# XTIDA-010086_Control_Card_28379.net
KiCad netlist of a schematic drawn in Altium Designer
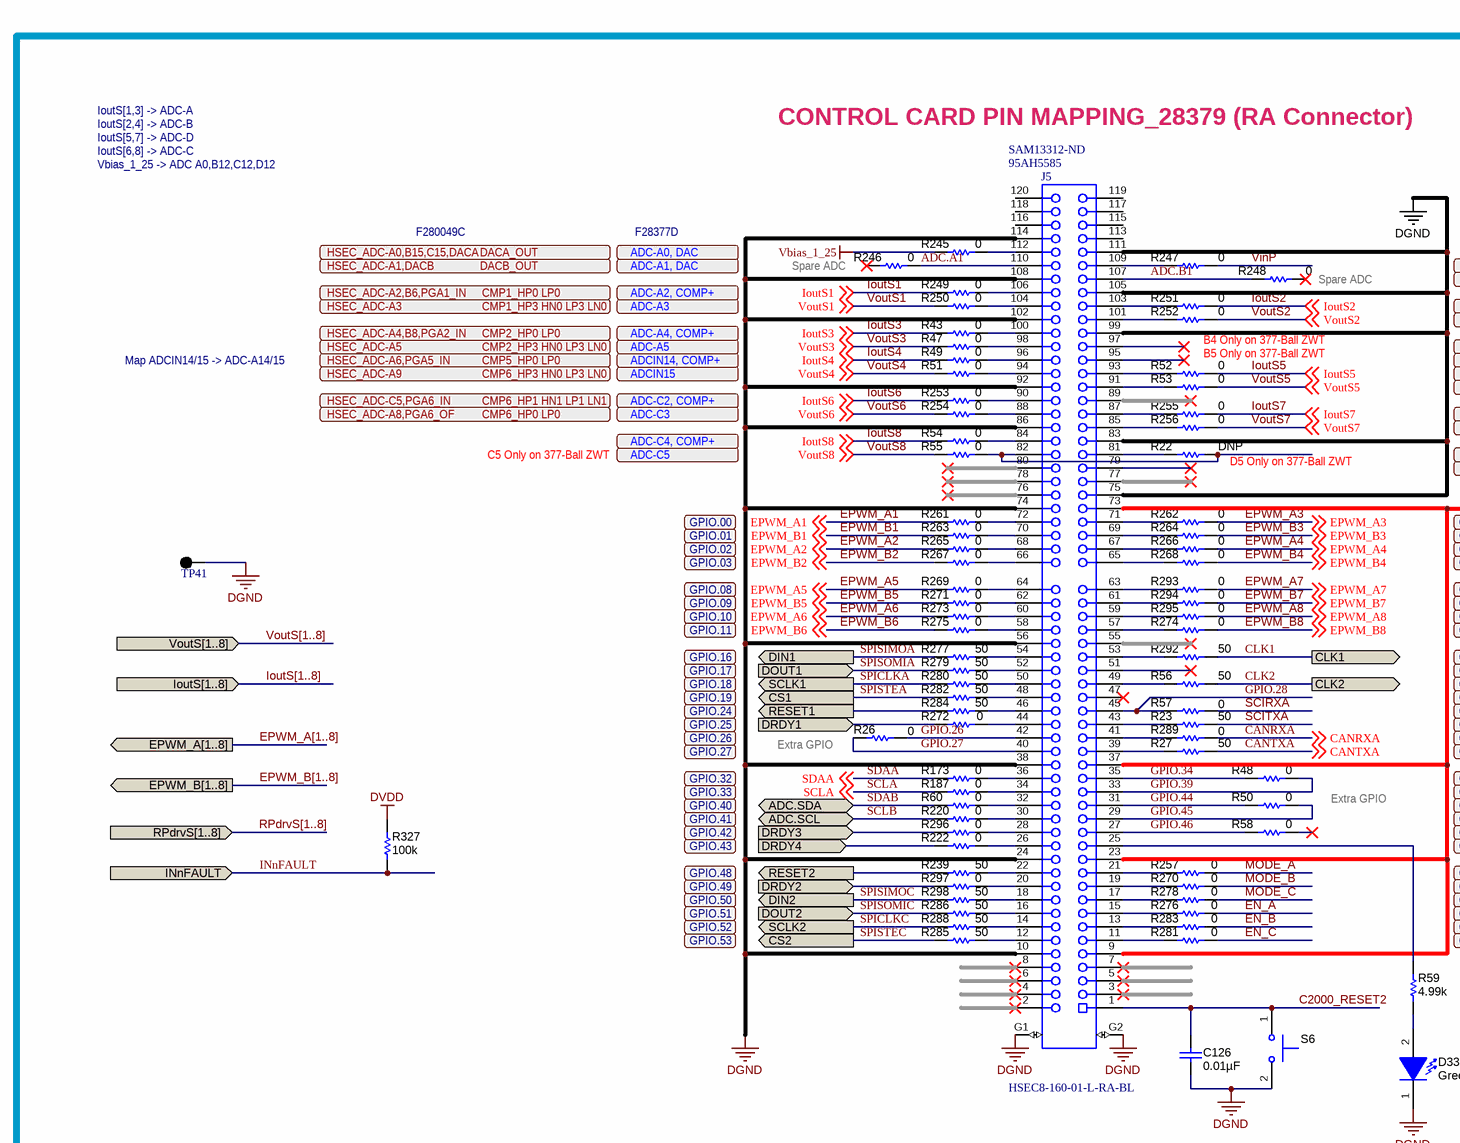
[diagram p0: XTIDA-010086_Control Card_28379.SchDoc, top left]
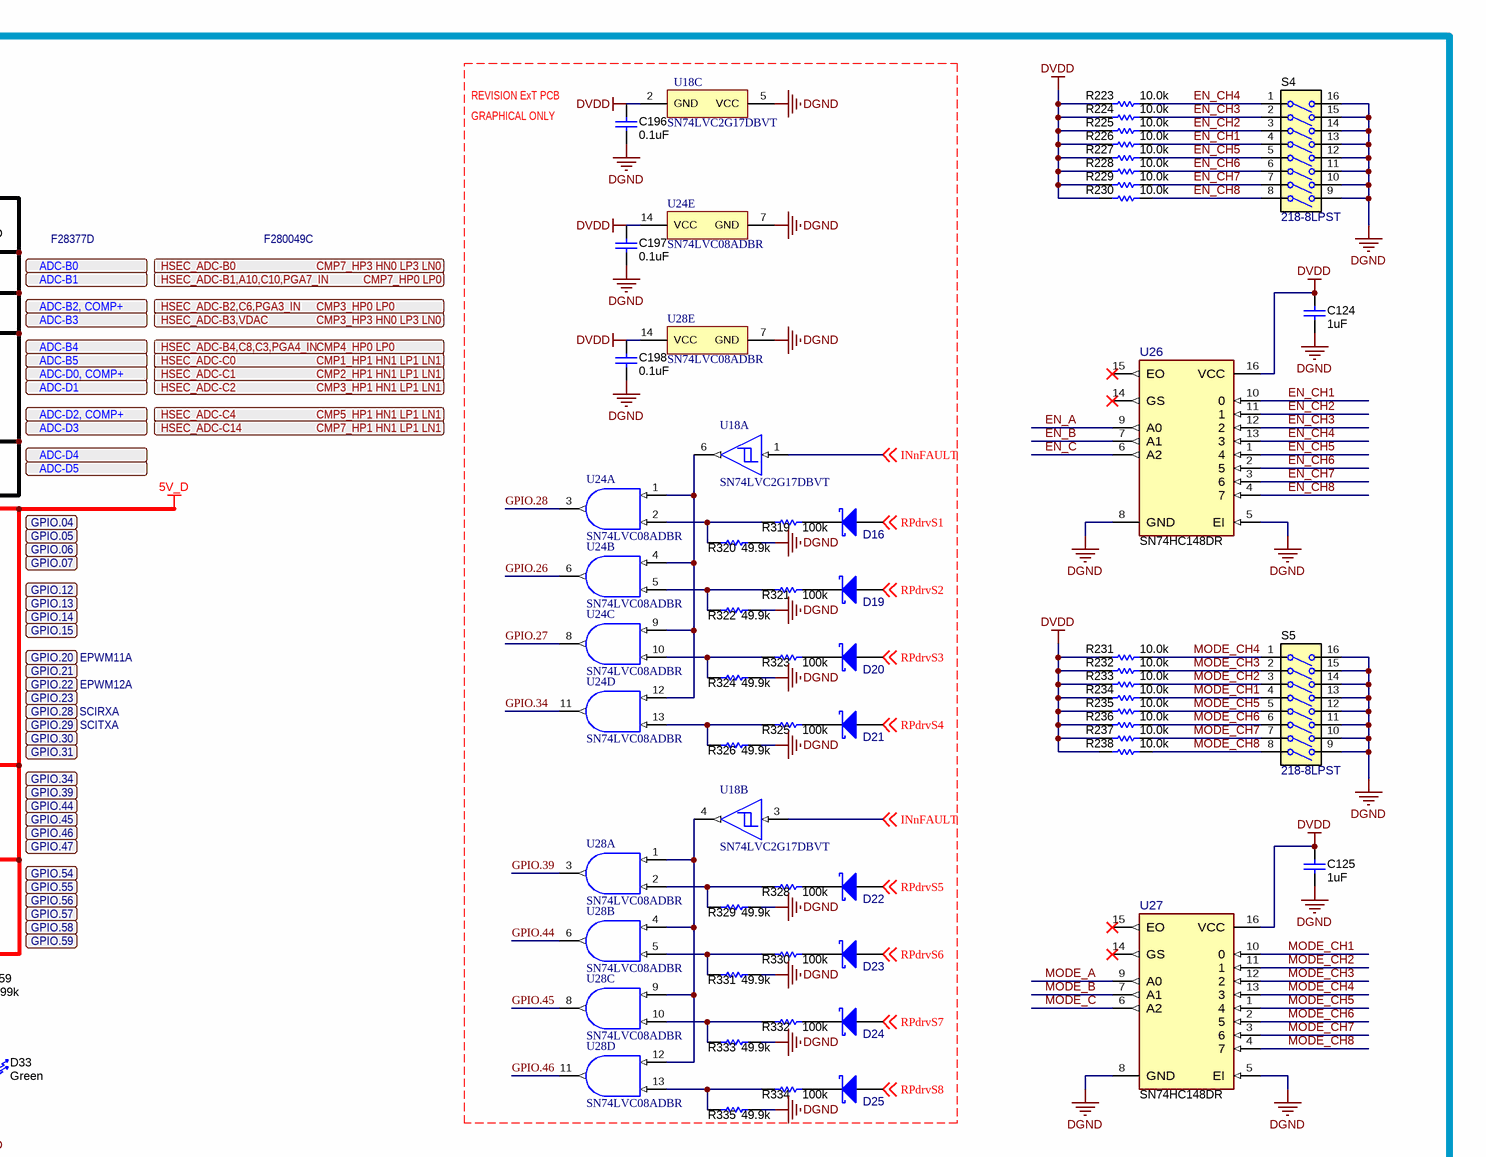
[diagram p1: XTIDA-010086_Control Card_28379.SchDoc, top right]
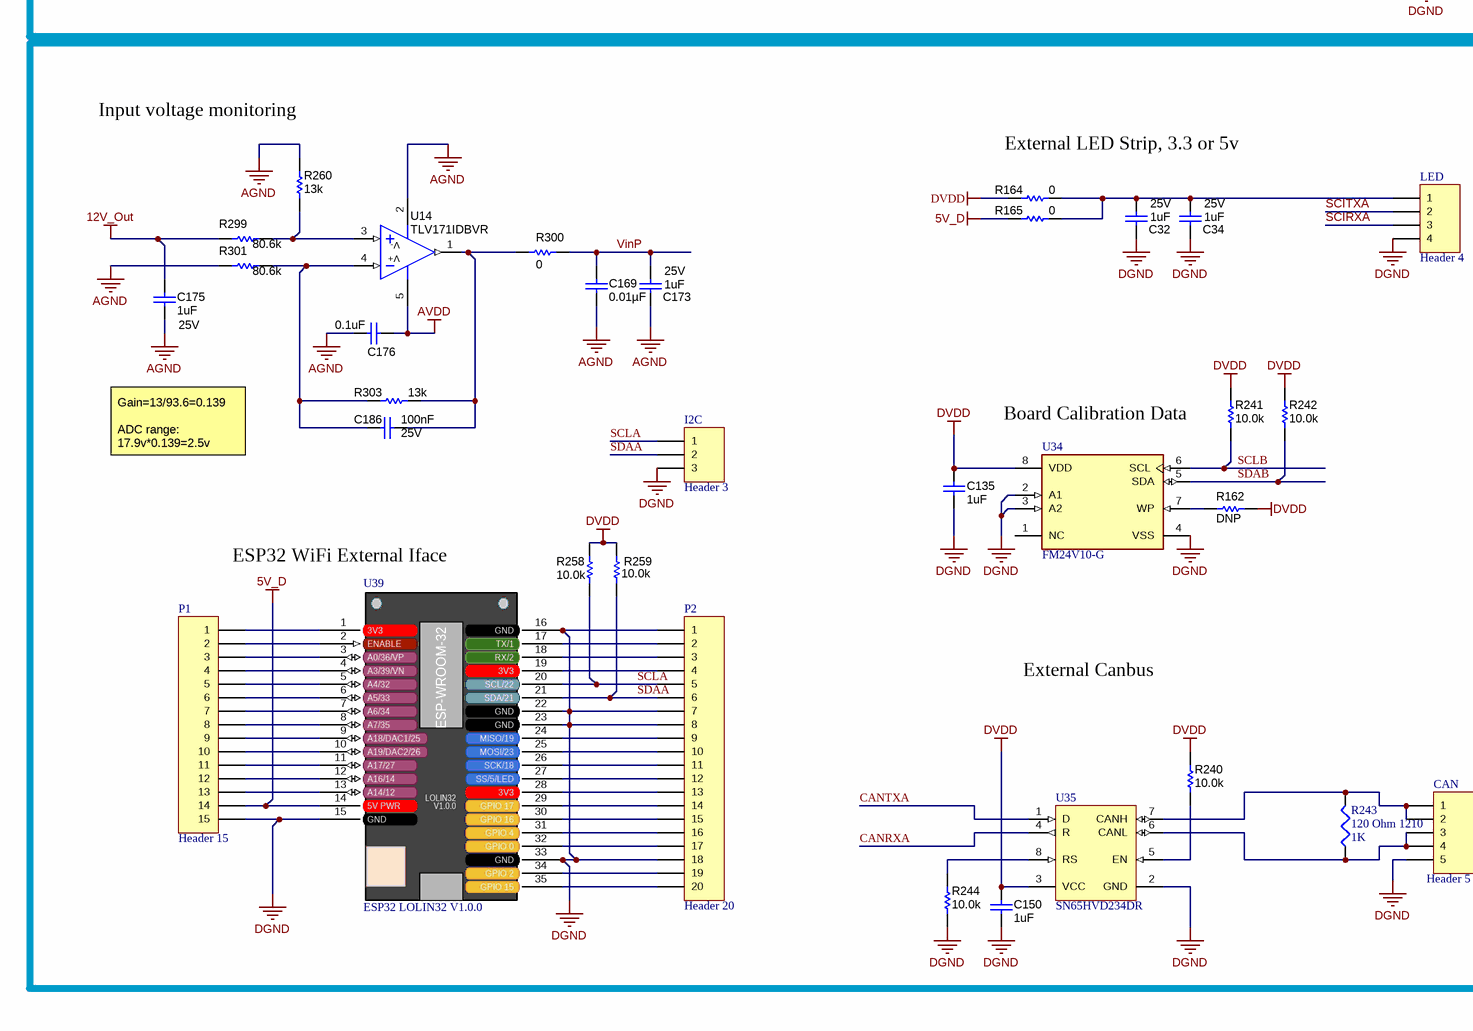
[diagram p2: XTIDA-010086_Control Card_28379.SchDoc, bottom left]
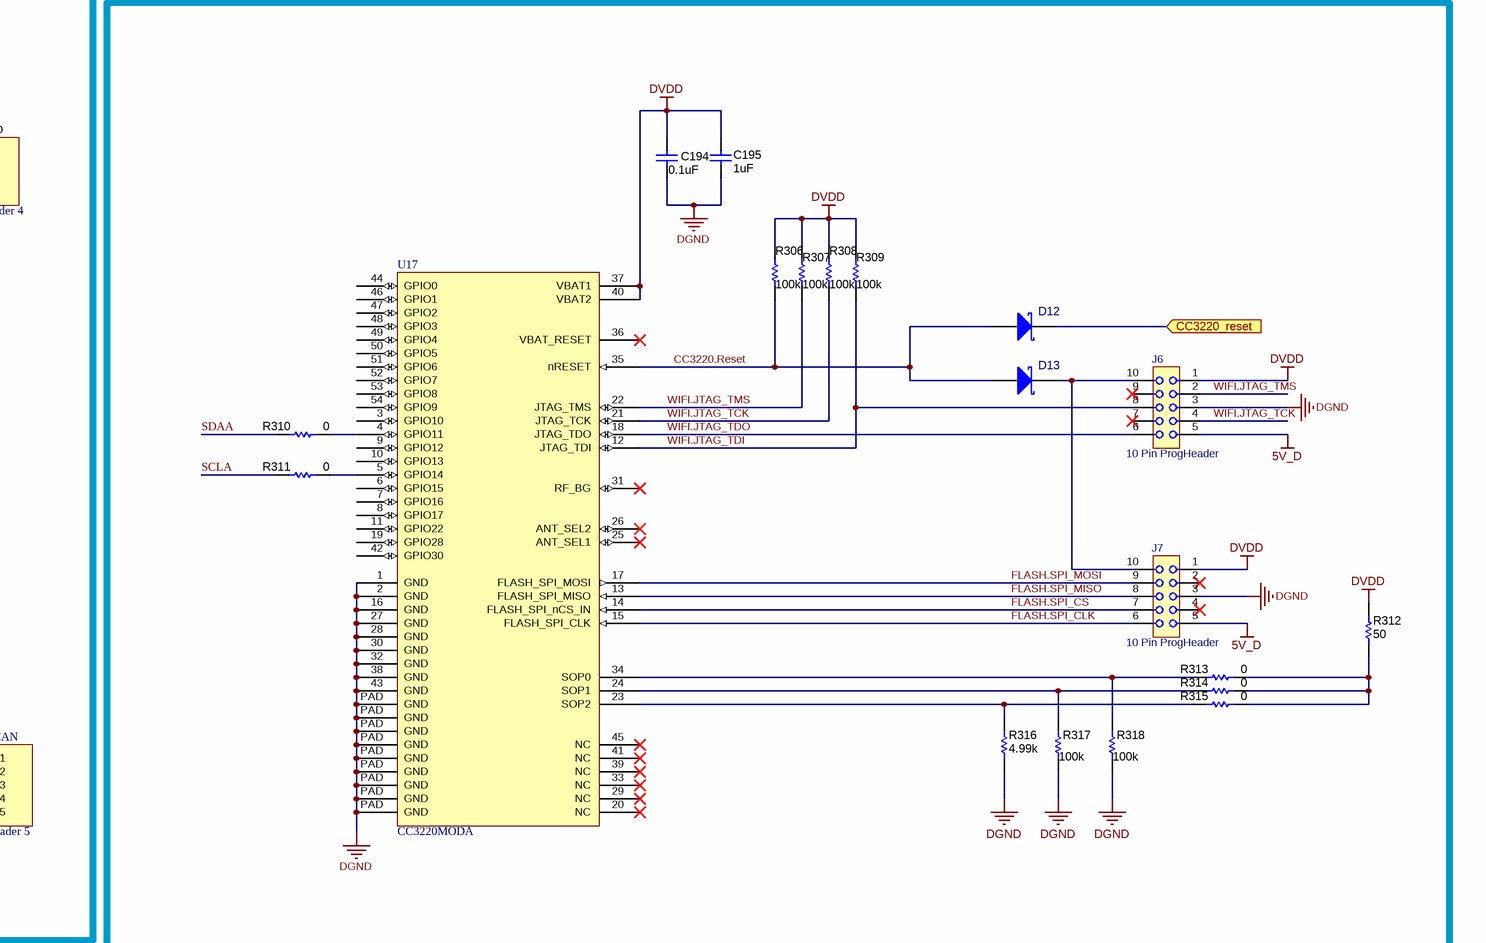
[diagram p3: XTIDA-010086_Control Card_28379.SchDoc, bottom right]

(export (version "E")
  (design (tool "Eeschema 10.0.6"))
  (components
    (comp (ref "C32")
      (value "GRM188R71E105KA12D")
      (footprint "0603")
      (description "CAP, CERM, 1 uF, 25 V, +/- 10%, X7R, 0603")
      (fields
        (field (name "VALUEDISPLAYED") "1uF")
        (field (name "MANUFACTURER") "MuRata")
        (field (name "VDC_V") "25V")
        (field (name "PUBLISHER") "Texas Instruments")
      )
      (libsource (lib "Capacitor_Ceramic") (part "Capacitor"))
    )
    (comp (ref "C34")
      (value "GRM188R71E105KA12D")
      (footprint "0603")
      (description "CAP, CERM, 1 uF, 25 V, +/- 10%, X7R, 0603")
      (fields
        (field (name "VALUEDISPLAYED") "1uF")
        (field (name "MANUFACTURER") "MuRata")
        (field (name "VDC_V") "25V")
        (field (name "PUBLISHER") "Texas Instruments")
      )
      (libsource (lib "Capacitor_Ceramic") (part "Capacitor"))
    )
    (comp (ref "C124")
      (value "GRM188R71E105KA12D")
      (footprint "0603")
      (description "CAP, CERM, 1 uF, 25 V, +/- 10%, X7R, 0603")
      (fields
        (field (name "VALUEDISPLAYED") "1uF")
        (field (name "MANUFACTURER") "MuRata")
        (field (name "PUBLISHER") "Texas Instruments")
      )
      (libsource (lib "Capacitor_Ceramic") (part "Capacitor"))
    )
    (comp (ref "C125")
      (value "GRM188R71E105KA12D")
      (footprint "0603")
      (description "CAP, CERM, 1 uF, 25 V, +/- 10%, X7R, 0603")
      (fields
        (field (name "VALUEDISPLAYED") "1uF")
        (field (name "MANUFACTURER") "MuRata")
        (field (name "PUBLISHER") "Texas Instruments")
      )
      (libsource (lib "Capacitor_Ceramic") (part "Capacitor"))
    )
    (comp (ref "C126")
      (value "C0603C103J3GECAUTO")
      (footprint "0603")
      (description "CAP, CERM, 0.01 µF, 25 V,+/- 5%, C0G/NP0, AEC-Q200 Grade 1, 0603")
      (fields
        (field (name "VALUEDISPLAYED") "0.01µF")
        (field (name "MANUFACTURER") "Kemet")
        (field (name "PUBLISHER") "Texas Instruments")
      )
      (libsource (lib "Capacitor_Ceramic") (part "C0603C103J3GECAUTO"))
    )
    (comp (ref "C135")
      (value "GRM188R71E105KA12D")
      (footprint "0603")
      (description "CAP, CERM, 1 uF, 25 V, +/- 10%, X7R, 0603")
      (fields
        (field (name "VALUEDISPLAYED") "1uF")
        (field (name "MANUFACTURER") "MuRata")
        (field (name "PUBLISHER") "Texas Instruments")
      )
      (libsource (lib "Capacitor_Ceramic") (part "Capacitor"))
    )
    (comp (ref "C150")
      (value "GRM188R71E105KA12D")
      (footprint "0603")
      (description "CAP, CERM, 1 uF, 25 V, +/- 10%, X7R, 0603")
      (fields
        (field (name "VALUEDISPLAYED") "1uF")
        (field (name "MANUFACTURER") "MuRata")
        (field (name "PUBLISHER") "Texas Instruments")
      )
      (libsource (lib "Capacitor_Ceramic") (part "Capacitor"))
    )
    (comp (ref "C169")
      (value "C0603C103J3GECAUTO")
      (footprint "0603")
      (description "CAP, CERM, 0.01 µF, 25 V,+/- 5%, C0G/NP0, AEC-Q200 Grade 1, 0603")
      (fields
        (field (name "VALUEDISPLAYED") "0.01µF")
        (field (name "MANUFACTURER") "Kemet")
        (field (name "PUBLISHER") "Texas Instruments")
      )
      (libsource (lib "Capacitor_Ceramic") (part "C0603C103J3GECAUTO"))
    )
    (comp (ref "C173")
      (value "GRM188R71E105KA12D")
      (footprint "0603")
      (description "CAP, CERM, 1 uF, 25 V, +/- 10%, X7R, 0603")
      (fields
        (field (name "VALUEDISPLAYED") "1uF")
        (field (name "MANUFACTURER") "MuRata")
        (field (name "VDC_V") "25V")
        (field (name "PUBLISHER") "Texas Instruments")
      )
      (libsource (lib "Capacitor_Ceramic") (part "Capacitor"))
    )
    (comp (ref "C175")
      (value "GRM188R71E105KA12D")
      (footprint "0603")
      (description "CAP, CERM, 1 uF, 25 V, +/- 10%, X7R, 0603")
      (fields
        (field (name "VALUEDISPLAYED") "1uF")
        (field (name "MANUFACTURER") "MuRata")
        (field (name "VALUE2") "25V")
        (field (name "PUBLISHER") "Texas Instruments")
      )
      (libsource (lib "Capacitor_Ceramic") (part "Capacitor"))
    )
    (comp (ref "C176")
      (value "06033C104JAT2A")
      (footprint "0603")
      (description "CAP, CERM, 0.1 uF, 25 V, +/- 5%, X7R, 0603")
      (fields
        (field (name "VALUEDISPLAYED") "0.1uF")
        (field (name "MANUFACTURER") "AVX")
        (field (name "PUBLISHER") "Texas Instruments")
      )
      (libsource (lib "TIDA-010086") (part "Capacitor"))
    )
    (comp (ref "C186")
      (value "06033C104JAT2A")
      (footprint "0603")
      (description "CAP, CERM, 0.1 uF, 25 V, +/- 5%, X7R, 0603")
      (fields
        (field (name "MANUFACTURER") "AVX")
        (field (name "CAP_F") "100nF")
        (field (name "VALUE2") "25V")
        (field (name "PUBLISHER") "Texas Instruments")
      )
      (libsource (lib "TIDA-010086") (part "Capacitor"))
    )
    (comp (ref "C194")
      (value "06033C104JAT2A")
      (footprint "0603")
      (description "CAP, CERM, 0.1 uF, 25 V, +/- 5%, X7R, 0603")
      (fields
        (field (name "VALUEDISPLAYED") "0.1uF")
        (field (name "MANUFACTURER") "AVX")
        (field (name "PUBLISHER") "Texas Instruments")
      )
      (libsource (lib "TIDA-010086") (part "Capacitor"))
    )
    (comp (ref "C195")
      (value "GRM188R71E105KA12D")
      (footprint "0603")
      (description "CAP, CERM, 1 uF, 25 V, +/- 10%, X7R, 0603")
      (fields
        (field (name "VALUEDISPLAYED") "1uF")
        (field (name "MANUFACTURER") "MuRata")
        (field (name "PUBLISHER") "Texas Instruments")
      )
      (libsource (lib "Capacitor_Ceramic") (part "Capacitor"))
    )
    (comp (ref "C196")
      (value "06033C104JAT2A")
      (footprint "0603")
      (description "CAP, CERM, 0.1 uF, 25 V, +/- 5%, X7R, 0603")
      (fields
        (field (name "VALUEDISPLAYED") "0.1uF")
        (field (name "MANUFACTURER") "AVX")
        (field (name "PUBLISHER") "Texas Instruments")
      )
      (libsource (lib "TIDA-010086") (part "Capacitor"))
    )
    (comp (ref "C197")
      (value "06033C104JAT2A")
      (footprint "0603")
      (description "CAP, CERM, 0.1 uF, 25 V, +/- 5%, X7R, 0603")
      (fields
        (field (name "VALUEDISPLAYED") "0.1uF")
        (field (name "MANUFACTURER") "AVX")
        (field (name "PUBLISHER") "Texas Instruments")
      )
      (libsource (lib "TIDA-010086") (part "Capacitor"))
    )
    (comp (ref "C198")
      (value "06033C104JAT2A")
      (footprint "0603")
      (description "CAP, CERM, 0.1 uF, 25 V, +/- 5%, X7R, 0603")
      (fields
        (field (name "VALUEDISPLAYED") "0.1uF")
        (field (name "MANUFACTURER") "AVX")
        (field (name "PUBLISHER") "Texas Instruments")
      )
      (libsource (lib "TIDA-010086") (part "Capacitor"))
    )
    (comp (ref "CAN")
      (value "Header 5")
      (footprint "TERM_BLK_ED555-5DS")
      (description "Header, 5-Pin")
      (fields (field (name "PUBLISHER") "Altium Limited"))
      (libsource (lib "Miscellaneous Connectors") (part "Header 5"))
    )
    (comp (ref "D12")
      (value "NSR0240V2T1G")
      (footprint "SOD-523")
      (description "Diode, Schottky, 40V, 0.25A, SOD-523")
      (fields (field (name "MANUFACTURER") "ON Semiconductor") (field (name "PUBLISHER") "Texas Instruments"))
      (libsource (lib "Diode") (part "NSR0240V2T1G"))
    )
    (comp (ref "D13")
      (value "NSR0240V2T1G")
      (footprint "SOD-523")
      (description "Diode, Schottky, 40V, 0.25A, SOD-523")
      (fields (field (name "MANUFACTURER") "ON Semiconductor") (field (name "PUBLISHER") "Texas Instruments"))
      (libsource (lib "Diode") (part "NSR0240V2T1G"))
    )
    (comp (ref "D16")
      (value "NSR0240V2T1G")
      (footprint "SOD-523")
      (description "Diode, Schottky, 40V, 0.25A, SOD-523")
      (fields (field (name "MANUFACTURER") "ON Semiconductor") (field (name "PUBLISHER") "Texas Instruments"))
      (libsource (lib "Diode") (part "NSR0240V2T1G"))
    )
    (comp (ref "D19")
      (value "NSR0240V2T1G")
      (footprint "SOD-523")
      (description "Diode, Schottky, 40V, 0.25A, SOD-523")
      (fields (field (name "MANUFACTURER") "ON Semiconductor") (field (name "PUBLISHER") "Texas Instruments"))
      (libsource (lib "Diode") (part "NSR0240V2T1G"))
    )
    (comp (ref "D20")
      (value "NSR0240V2T1G")
      (footprint "SOD-523")
      (description "Diode, Schottky, 40V, 0.25A, SOD-523")
      (fields (field (name "MANUFACTURER") "ON Semiconductor") (field (name "PUBLISHER") "Texas Instruments"))
      (libsource (lib "Diode") (part "NSR0240V2T1G"))
    )
    (comp (ref "D21")
      (value "NSR0240V2T1G")
      (footprint "SOD-523")
      (description "Diode, Schottky, 40V, 0.25A, SOD-523")
      (fields (field (name "MANUFACTURER") "ON Semiconductor") (field (name "PUBLISHER") "Texas Instruments"))
      (libsource (lib "Diode") (part "NSR0240V2T1G"))
    )
    (comp (ref "D22")
      (value "NSR0240V2T1G")
      (footprint "SOD-523")
      (description "Diode, Schottky, 40V, 0.25A, SOD-523")
      (fields (field (name "MANUFACTURER") "ON Semiconductor") (field (name "PUBLISHER") "Texas Instruments"))
      (libsource (lib "Diode") (part "NSR0240V2T1G"))
    )
    (comp (ref "D23")
      (value "NSR0240V2T1G")
      (footprint "SOD-523")
      (description "Diode, Schottky, 40V, 0.25A, SOD-523")
      (fields (field (name "MANUFACTURER") "ON Semiconductor") (field (name "PUBLISHER") "Texas Instruments"))
      (libsource (lib "Diode") (part "NSR0240V2T1G"))
    )
    (comp (ref "D24")
      (value "NSR0240V2T1G")
      (footprint "SOD-523")
      (description "Diode, Schottky, 40V, 0.25A, SOD-523")
      (fields (field (name "MANUFACTURER") "ON Semiconductor") (field (name "PUBLISHER") "Texas Instruments"))
      (libsource (lib "Diode") (part "NSR0240V2T1G"))
    )
    (comp (ref "D25")
      (value "NSR0240V2T1G")
      (footprint "SOD-523")
      (description "Diode, Schottky, 40V, 0.25A, SOD-523")
      (fields (field (name "MANUFACTURER") "ON Semiconductor") (field (name "PUBLISHER") "Texas Instruments"))
      (libsource (lib "Diode") (part "NSR0240V2T1G"))
    )
    (comp (ref "D33")
      (value "Green")
      (footprint "WL-SMCW_GREEN")
      (description "LED, Green, SMD")
      (fields
        (field (name "MANUFACTURER") "Wurth Elektronik")
        (field (name "PARTNUMBER") "150060VS75000")
        (field (name "PUBLISHER") "Texas Instruments")
      )
      (libsource (lib "LED") (part "150060VS75000"))
    )
    (comp (ref "I2C")
      (value "Header 3")
      (footprint "TERM_BLK_ED555-3DS")
      (description "Header, 3-Pin")
      (fields (field (name "PUBLISHER") "Altium Limited"))
      (libsource (lib "Miscellaneous Connectors") (part "Header 3"))
    )
    (comp (ref "J5")
      (value "HSEC8-160-01-L-RA-BL")
      (footprint "HSEC8-160-01-X-RA-BL")
      (description "0.8MM HIGH SPEED ASSEMBLY.")
      (fields
        (field (name "MP") "HSEC8-160-01-X-RA-BL")
        (field (name "SUPPLIER PART NUMBER 1") "95AH5585")
        (field (name "SUPPLIER PART NUMBER 2") "SAM13312-ND")
      )
      (libsource (lib "TIDA-010086") (part "HSEC8-160-01-X-RA-BL"))
    )
    (comp (ref "J6")
      (value "10 Pin ProgHeader")
      (footprint "TC2050-NL-SMD_W/MOUNT")
      (description "do not populate, RoHS compliant")
      (libsource (lib "Ongyi") (part "10 Pin ProgHeader"))
    )
    (comp (ref "J7")
      (value "10 Pin ProgHeader")
      (footprint "TC2050-NL-SMD_W/mount")
      (description "do not populate, RoHS compliant")
      (libsource (lib "Ongyi") (part "10 Pin ProgHeader"))
    )
    (comp (ref "LED")
      (value "Header 4")
      (footprint "TERM_BLK_ED555-4DS")
      (description "Header, 4-Pin")
      (fields (field (name "PUBLISHER") "Altium Limited"))
      (libsource (lib "Miscellaneous Connectors") (part "Header 4"))
    )
    (comp (ref "P1")
      (value "Header 15")
      (footprint "HDR1X15")
      (description "Header, 15-Pin")
      (fields (field (name "PUBLISHER") "Altium Limited"))
      (libsource (lib "Miscellaneous Connectors") (part "Header 15"))
    )
    (comp (ref "P2")
      (value "Header 20")
      (footprint "HDR1X20")
      (description "Header, 20-Pin")
      (fields (field (name "PUBLISHER") "Altium Limited"))
      (libsource (lib "Miscellaneous Connectors") (part "Header 20"))
    )
    (comp (ref "R22")
      (value "CRCW04020000Z0ED")
      (footprint "0402")
      (description "RES, 0, 5%, 0.063 W, 0402")
      (fields
        (field (name "VALUEDISPLAYED") "DNP")
        (field (name "MANUFACTURER") "Vishay-Dale")
        (field (name "PUBLISHER") "Texas Instruments")
      )
      (libsource (lib "Resistor_0402") (part "CRCW04020000Z0ED"))
    )
    (comp (ref "R23")
      (value "FC0402E50R0BST1")
      (footprint "0402")
      (description "RES, 50, 0.1%, 0.05 W, 0402")
      (fields
        (field (name "VALUEDISPLAYED") "50")
        (field (name "MANUFACTURER") "Vishay-Dale")
        (field (name "PUBLISHER") "Texas Instruments")
      )
      (libsource (lib "Resistor_0402") (part "FC0402E50R0BST1"))
    )
    (comp (ref "R26")
      (value "CRCW04020000Z0ED")
      (footprint "0402")
      (description "RES, 0, 5%, 0.063 W, 0402")
      (fields
        (field (name "VALUEDISPLAYED") "0")
        (field (name "MANUFACTURER") "Vishay-Dale")
        (field (name "PUBLISHER") "Texas Instruments")
      )
      (libsource (lib "Resistor_0402") (part "CRCW04020000Z0ED"))
    )
    (comp (ref "R27")
      (value "FC0402E50R0BST1")
      (footprint "0402")
      (description "RES, 50, 0.1%, 0.05 W, 0402")
      (fields
        (field (name "VALUEDISPLAYED") "50")
        (field (name "MANUFACTURER") "Vishay-Dale")
        (field (name "PUBLISHER") "Texas Instruments")
      )
      (libsource (lib "Resistor_0402") (part "FC0402E50R0BST1"))
    )
    (comp (ref "R43")
      (value "CRCW04020000Z0ED")
      (footprint "0402")
      (description "RES, 0, 5%, 0.063 W, 0402")
      (fields
        (field (name "VALUEDISPLAYED") "0")
        (field (name "MANUFACTURER") "Vishay-Dale")
        (field (name "PUBLISHER") "Texas Instruments")
      )
      (libsource (lib "Resistor_0402") (part "CRCW04020000Z0ED"))
    )
    (comp (ref "R47")
      (value "CRCW04020000Z0ED")
      (footprint "0402")
      (description "RES, 0, 5%, 0.063 W, 0402")
      (fields
        (field (name "VALUEDISPLAYED") "0")
        (field (name "MANUFACTURER") "Vishay-Dale")
        (field (name "PUBLISHER") "Texas Instruments")
      )
      (libsource (lib "Resistor_0402") (part "CRCW04020000Z0ED"))
    )
    (comp (ref "R48")
      (value "CRCW04020000Z0ED")
      (footprint "0402")
      (description "RES, 0, 5%, 0.063 W, 0402")
      (fields
        (field (name "VALUEDISPLAYED") "0")
        (field (name "MANUFACTURER") "Vishay-Dale")
        (field (name "PUBLISHER") "Texas Instruments")
      )
      (libsource (lib "Resistor_0402") (part "CRCW04020000Z0ED"))
    )
    (comp (ref "R49")
      (value "CRCW04020000Z0ED")
      (footprint "0402")
      (description "RES, 0, 5%, 0.063 W, 0402")
      (fields
        (field (name "VALUEDISPLAYED") "0")
        (field (name "MANUFACTURER") "Vishay-Dale")
        (field (name "PUBLISHER") "Texas Instruments")
      )
      (libsource (lib "Resistor_0402") (part "CRCW04020000Z0ED"))
    )
    (comp (ref "R50")
      (value "CRCW04020000Z0ED")
      (footprint "0402")
      (description "RES, 0, 5%, 0.063 W, 0402")
      (fields
        (field (name "VALUEDISPLAYED") "0")
        (field (name "MANUFACTURER") "Vishay-Dale")
        (field (name "PUBLISHER") "Texas Instruments")
      )
      (libsource (lib "Resistor_0402") (part "CRCW04020000Z0ED"))
    )
    (comp (ref "R51")
      (value "CRCW04020000Z0ED")
      (footprint "0402")
      (description "RES, 0, 5%, 0.063 W, 0402")
      (fields
        (field (name "VALUEDISPLAYED") "0")
        (field (name "MANUFACTURER") "Vishay-Dale")
        (field (name "PUBLISHER") "Texas Instruments")
      )
      (libsource (lib "Resistor_0402") (part "CRCW04020000Z0ED"))
    )
    (comp (ref "R52")
      (value "CRCW04020000Z0ED")
      (footprint "0402")
      (description "RES, 0, 5%, 0.063 W, 0402")
      (fields
        (field (name "VALUEDISPLAYED") "0")
        (field (name "MANUFACTURER") "Vishay-Dale")
        (field (name "PUBLISHER") "Texas Instruments")
      )
      (libsource (lib "Resistor_0402") (part "CRCW04020000Z0ED"))
    )
    (comp (ref "R53")
      (value "CRCW04020000Z0ED")
      (footprint "0402")
      (description "RES, 0, 5%, 0.063 W, 0402")
      (fields
        (field (name "VALUEDISPLAYED") "0")
        (field (name "MANUFACTURER") "Vishay-Dale")
        (field (name "PUBLISHER") "Texas Instruments")
      )
      (libsource (lib "Resistor_0402") (part "CRCW04020000Z0ED"))
    )
    (comp (ref "R54")
      (value "CRCW04020000Z0ED")
      (footprint "0402")
      (description "RES, 0, 5%, 0.063 W, 0402")
      (fields
        (field (name "VALUEDISPLAYED") "0")
        (field (name "MANUFACTURER") "Vishay-Dale")
        (field (name "PUBLISHER") "Texas Instruments")
      )
      (libsource (lib "Resistor_0402") (part "CRCW04020000Z0ED"))
    )
    (comp (ref "R55")
      (value "CRCW04020000Z0ED")
      (footprint "0402")
      (description "RES, 0, 5%, 0.063 W, 0402")
      (fields
        (field (name "VALUEDISPLAYED") "0")
        (field (name "MANUFACTURER") "Vishay-Dale")
        (field (name "PUBLISHER") "Texas Instruments")
      )
      (libsource (lib "Resistor_0402") (part "CRCW04020000Z0ED"))
    )
    (comp (ref "R56")
      (value "FC0402E50R0BST1")
      (footprint "0402")
      (description "RES, 50, 0.1%, 0.05 W, 0402")
      (fields
        (field (name "VALUEDISPLAYED") "50")
        (field (name "MANUFACTURER") "Vishay-Dale")
        (field (name "PUBLISHER") "Texas Instruments")
      )
      (libsource (lib "Resistor_0402") (part "FC0402E50R0BST1"))
    )
    (comp (ref "R57")
      (value "CRCW04020000Z0ED")
      (footprint "0402")
      (description "RES, 0, 5%, 0.063 W, 0402")
      (fields
        (field (name "VALUEDISPLAYED") "0")
        (field (name "MANUFACTURER") "Vishay-Dale")
        (field (name "PUBLISHER") "Texas Instruments")
      )
      (libsource (lib "Resistor_0402") (part "CRCW04020000Z0ED"))
    )
    (comp (ref "R58")
      (value "CRCW04020000Z0ED")
      (footprint "0402")
      (description "RES, 0, 5%, 0.063 W, 0402")
      (fields
        (field (name "VALUEDISPLAYED") "0")
        (field (name "MANUFACTURER") "Vishay-Dale")
        (field (name "PUBLISHER") "Texas Instruments")
      )
      (libsource (lib "Resistor_0402") (part "CRCW04020000Z0ED"))
    )
    (comp (ref "R59")
      (value "CRCW06034K99FKEA")
      (footprint "0603L")
      (description "RES, 4.99 k, 1%, 0.1 W, 0603")
      (fields
        (field (name "VALUEDISPLAYED") "4.99k")
        (field (name "MANUFACTURER") "Vishay-Dale")
        (field (name "PUBLISHER") "Texas Instruments")
      )
      (libsource (lib "Resistor_0603") (part "CRCW06034K99FKEA"))
    )
    (comp (ref "R60")
      (value "CRCW04020000Z0ED")
      (footprint "0402")
      (description "RES, 0, 5%, 0.063 W, 0402")
      (fields
        (field (name "VALUEDISPLAYED") "0")
        (field (name "MANUFACTURER") "Vishay-Dale")
        (field (name "PUBLISHER") "Texas Instruments")
      )
      (libsource (lib "Resistor_0402") (part "CRCW04020000Z0ED"))
    )
    (comp (ref "R162")
      (value "CRCW04020000Z0ED")
      (footprint "0402")
      (description "RES, 0, 5%, 0.063 W, 0402")
      (fields
        (field (name "VALUEDISPLAYED") "DNP")
        (field (name "MANUFACTURER") "Vishay-Dale")
        (field (name "PUBLISHER") "Texas Instruments")
      )
      (libsource (lib "Resistor_0402") (part "CRCW04020000Z0ED"))
    )
    (comp (ref "R164")
      (value "CRCW04020000Z0ED")
      (footprint "0402")
      (description "RES, 0, 5%, 0.063 W, 0402")
      (fields
        (field (name "VALUEDISPLAYED") "0")
        (field (name "MANUFACTURER") "Vishay-Dale")
        (field (name "PUBLISHER") "Texas Instruments")
      )
      (libsource (lib "Resistor_0402") (part "CRCW04020000Z0ED"))
    )
    (comp (ref "R165")
      (value "CRCW04020000Z0ED")
      (footprint "0402")
      (description "RES, 0, 5%, 0.063 W, 0402")
      (fields
        (field (name "VALUEDISPLAYED") "0")
        (field (name "MANUFACTURER") "Vishay-Dale")
        (field (name "PUBLISHER") "Texas Instruments")
      )
      (libsource (lib "Resistor_0402") (part "CRCW04020000Z0ED"))
    )
    (comp (ref "R173")
      (value "CRCW04020000Z0ED")
      (footprint "0402")
      (description "RES, 0, 5%, 0.063 W, 0402")
      (fields
        (field (name "VALUEDISPLAYED") "0")
        (field (name "MANUFACTURER") "Vishay-Dale")
        (field (name "PUBLISHER") "Texas Instruments")
      )
      (libsource (lib "Resistor_0402") (part "CRCW04020000Z0ED"))
    )
    (comp (ref "R187")
      (value "CRCW04020000Z0ED")
      (footprint "0402")
      (description "RES, 0, 5%, 0.063 W, 0402")
      (fields
        (field (name "VALUEDISPLAYED") "0")
        (field (name "MANUFACTURER") "Vishay-Dale")
        (field (name "PUBLISHER") "Texas Instruments")
      )
      (libsource (lib "Resistor_0402") (part "CRCW04020000Z0ED"))
    )
    (comp (ref "R220")
      (value "CRCW04020000Z0ED")
      (footprint "0402")
      (description "RES, 0, 5%, 0.063 W, 0402")
      (fields
        (field (name "VALUEDISPLAYED") "0")
        (field (name "MANUFACTURER") "Vishay-Dale")
        (field (name "PUBLISHER") "Texas Instruments")
      )
      (libsource (lib "Resistor_0402") (part "CRCW04020000Z0ED"))
    )
    (comp (ref "R222")
      (value "CRCW04020000Z0ED")
      (footprint "0402")
      (description "RES, 0, 5%, 0.063 W, 0402")
      (fields
        (field (name "VALUEDISPLAYED") "0")
        (field (name "MANUFACTURER") "Vishay-Dale")
        (field (name "PUBLISHER") "Texas Instruments")
      )
      (libsource (lib "Resistor_0402") (part "CRCW04020000Z0ED"))
    )
    (comp (ref "R223")
      (value "CRCW040210K0FKED")
      (footprint "0402")
      (description "RES, 10.0 k, 1%, 0.063 W, 0402")
      (fields
        (field (name "VALUEDISPLAYED") "10.0k")
        (field (name "MANUFACTURER") "Vishay-Dale")
        (field (name "PUBLISHER") "Texas Instruments")
      )
      (libsource (lib "Resistor_0402") (part "CRCW040210K0FKED"))
    )
    (comp (ref "R224")
      (value "CRCW040210K0FKED")
      (footprint "0402")
      (description "RES, 10.0 k, 1%, 0.063 W, 0402")
      (fields
        (field (name "VALUEDISPLAYED") "10.0k")
        (field (name "MANUFACTURER") "Vishay-Dale")
        (field (name "PUBLISHER") "Texas Instruments")
      )
      (libsource (lib "Resistor_0402") (part "CRCW040210K0FKED"))
    )
    (comp (ref "R225")
      (value "CRCW040210K0FKED")
      (footprint "0402")
      (description "RES, 10.0 k, 1%, 0.063 W, 0402")
      (fields
        (field (name "VALUEDISPLAYED") "10.0k")
        (field (name "MANUFACTURER") "Vishay-Dale")
        (field (name "PUBLISHER") "Texas Instruments")
      )
      (libsource (lib "Resistor_0402") (part "CRCW040210K0FKED"))
    )
    (comp (ref "R226")
      (value "CRCW040210K0FKED")
      (footprint "0402")
      (description "RES, 10.0 k, 1%, 0.063 W, 0402")
      (fields
        (field (name "VALUEDISPLAYED") "10.0k")
        (field (name "MANUFACTURER") "Vishay-Dale")
        (field (name "PUBLISHER") "Texas Instruments")
      )
      (libsource (lib "Resistor_0402") (part "CRCW040210K0FKED"))
    )
    (comp (ref "R227")
      (value "CRCW040210K0FKED")
      (footprint "0402")
      (description "RES, 10.0 k, 1%, 0.063 W, 0402")
      (fields
        (field (name "VALUEDISPLAYED") "10.0k")
        (field (name "MANUFACTURER") "Vishay-Dale")
        (field (name "PUBLISHER") "Texas Instruments")
      )
      (libsource (lib "Resistor_0402") (part "CRCW040210K0FKED"))
    )
    (comp (ref "R228")
      (value "CRCW040210K0FKED")
      (footprint "0402")
      (description "RES, 10.0 k, 1%, 0.063 W, 0402")
      (fields
        (field (name "VALUEDISPLAYED") "10.0k")
        (field (name "MANUFACTURER") "Vishay-Dale")
        (field (name "PUBLISHER") "Texas Instruments")
      )
      (libsource (lib "Resistor_0402") (part "CRCW040210K0FKED"))
    )
    (comp (ref "R229")
      (value "CRCW040210K0FKED")
      (footprint "0402")
      (description "RES, 10.0 k, 1%, 0.063 W, 0402")
      (fields
        (field (name "VALUEDISPLAYED") "10.0k")
        (field (name "MANUFACTURER") "Vishay-Dale")
        (field (name "PUBLISHER") "Texas Instruments")
      )
      (libsource (lib "Resistor_0402") (part "CRCW040210K0FKED"))
    )
    (comp (ref "R230")
      (value "CRCW040210K0FKED")
      (footprint "0402")
      (description "RES, 10.0 k, 1%, 0.063 W, 0402")
      (fields
        (field (name "VALUEDISPLAYED") "10.0k")
        (field (name "MANUFACTURER") "Vishay-Dale")
        (field (name "PUBLISHER") "Texas Instruments")
      )
      (libsource (lib "Resistor_0402") (part "CRCW040210K0FKED"))
    )
    (comp (ref "R231")
      (value "CRCW040210K0FKED")
      (footprint "0402")
      (description "RES, 10.0 k, 1%, 0.063 W, 0402")
      (fields
        (field (name "VALUEDISPLAYED") "10.0k")
        (field (name "MANUFACTURER") "Vishay-Dale")
        (field (name "PUBLISHER") "Texas Instruments")
      )
      (libsource (lib "Resistor_0402") (part "CRCW040210K0FKED"))
    )
    (comp (ref "R232")
      (value "CRCW040210K0FKED")
      (footprint "0402")
      (description "RES, 10.0 k, 1%, 0.063 W, 0402")
      (fields
        (field (name "VALUEDISPLAYED") "10.0k")
        (field (name "MANUFACTURER") "Vishay-Dale")
        (field (name "PUBLISHER") "Texas Instruments")
      )
      (libsource (lib "Resistor_0402") (part "CRCW040210K0FKED"))
    )
    (comp (ref "R233")
      (value "CRCW040210K0FKED")
      (footprint "0402")
      (description "RES, 10.0 k, 1%, 0.063 W, 0402")
      (fields
        (field (name "VALUEDISPLAYED") "10.0k")
        (field (name "MANUFACTURER") "Vishay-Dale")
        (field (name "PUBLISHER") "Texas Instruments")
      )
      (libsource (lib "Resistor_0402") (part "CRCW040210K0FKED"))
    )
    (comp (ref "R234")
      (value "CRCW040210K0FKED")
      (footprint "0402")
      (description "RES, 10.0 k, 1%, 0.063 W, 0402")
      (fields
        (field (name "VALUEDISPLAYED") "10.0k")
        (field (name "MANUFACTURER") "Vishay-Dale")
        (field (name "PUBLISHER") "Texas Instruments")
      )
      (libsource (lib "Resistor_0402") (part "CRCW040210K0FKED"))
    )
    (comp (ref "R235")
      (value "CRCW040210K0FKED")
      (footprint "0402")
      (description "RES, 10.0 k, 1%, 0.063 W, 0402")
      (fields
        (field (name "VALUEDISPLAYED") "10.0k")
        (field (name "MANUFACTURER") "Vishay-Dale")
        (field (name "PUBLISHER") "Texas Instruments")
      )
      (libsource (lib "Resistor_0402") (part "CRCW040210K0FKED"))
    )
    (comp (ref "R236")
      (value "CRCW040210K0FKED")
      (footprint "0402")
      (description "RES, 10.0 k, 1%, 0.063 W, 0402")
      (fields
        (field (name "VALUEDISPLAYED") "10.0k")
        (field (name "MANUFACTURER") "Vishay-Dale")
        (field (name "PUBLISHER") "Texas Instruments")
      )
      (libsource (lib "Resistor_0402") (part "CRCW040210K0FKED"))
    )
    (comp (ref "R237")
      (value "CRCW040210K0FKED")
      (footprint "0402")
      (description "RES, 10.0 k, 1%, 0.063 W, 0402")
      (fields
        (field (name "VALUEDISPLAYED") "10.0k")
        (field (name "MANUFACTURER") "Vishay-Dale")
        (field (name "PUBLISHER") "Texas Instruments")
      )
      (libsource (lib "Resistor_0402") (part "CRCW040210K0FKED"))
    )
    (comp (ref "R238")
      (value "CRCW040210K0FKED")
      (footprint "0402")
      (description "RES, 10.0 k, 1%, 0.063 W, 0402")
      (fields
        (field (name "VALUEDISPLAYED") "10.0k")
        (field (name "MANUFACTURER") "Vishay-Dale")
        (field (name "PUBLISHER") "Texas Instruments")
      )
      (libsource (lib "Resistor_0402") (part "CRCW040210K0FKED"))
    )
    (comp (ref "R239")
      (value "FC0402E50R0BST1")
      (footprint "0402")
      (description "RES, 50, 0.1%, 0.05 W, 0402")
      (fields
        (field (name "VALUEDISPLAYED") "50")
        (field (name "MANUFACTURER") "Vishay-Dale")
        (field (name "PUBLISHER") "Texas Instruments")
      )
      (libsource (lib "Resistor_0402") (part "FC0402E50R0BST1"))
    )
    (comp (ref "R240")
      (value "CRCW040210K0FKED")
      (footprint "0402")
      (description "RES, 10.0 k, 1%, 0.063 W, 0402")
      (fields
        (field (name "VALUEDISPLAYED") "10.0k")
        (field (name "MANUFACTURER") "Vishay-Dale")
        (field (name "PUBLISHER") "Texas Instruments")
      )
      (libsource (lib "Resistor_0402") (part "CRCW040210K0FKED"))
    )
    (comp (ref "R241")
      (value "CRCW040210K0FKED")
      (footprint "0402")
      (description "RES, 10.0 k, 1%, 0.063 W, 0402")
      (fields
        (field (name "VALUEDISPLAYED") "10.0k")
        (field (name "MANUFACTURER") "Vishay-Dale")
        (field (name "PUBLISHER") "Texas Instruments")
      )
      (libsource (lib "Resistor_0402") (part "CRCW040210K0FKED"))
    )
    (comp (ref "R242")
      (value "CRCW040210K0FKED")
      (footprint "0402")
      (description "RES, 10.0 k, 1%, 0.063 W, 0402")
      (fields
        (field (name "VALUEDISPLAYED") "10.0k")
        (field (name "MANUFACTURER") "Vishay-Dale")
        (field (name "PUBLISHER") "Texas Instruments")
      )
      (libsource (lib "Resistor_0402") (part "CRCW040210K0FKED"))
    )
    (comp (ref "R243")
      (value "120 Ohm 1210")
      (footprint "14-1210")
      (fields (field (name "ALTIUM_VALUE") "1K") (field (name "PUBLISHER") "Altium Limited"))
      (libsource (lib "Miscellaneous Devices") (part "Res3"))
    )
    (comp (ref "R244")
      (value "CRCW040210K0FKED")
      (footprint "0402")
      (description "RES, 10.0 k, 1%, 0.063 W, 0402")
      (fields
        (field (name "VALUEDISPLAYED") "10.0k")
        (field (name "MANUFACTURER") "Vishay-Dale")
        (field (name "PUBLISHER") "Texas Instruments")
      )
      (libsource (lib "Resistor_0402") (part "CRCW040210K0FKED"))
    )
    (comp (ref "R245")
      (value "CRCW04020000Z0ED")
      (footprint "0402")
      (description "RES, 0, 5%, 0.063 W, 0402")
      (fields
        (field (name "VALUEDISPLAYED") "0")
        (field (name "MANUFACTURER") "Vishay-Dale")
        (field (name "PUBLISHER") "Texas Instruments")
      )
      (libsource (lib "Resistor_0402") (part "CRCW04020000Z0ED"))
    )
    (comp (ref "R246")
      (value "CRCW04020000Z0ED")
      (footprint "0402")
      (description "RES, 0, 5%, 0.063 W, 0402")
      (fields
        (field (name "VALUEDISPLAYED") "0")
        (field (name "MANUFACTURER") "Vishay-Dale")
        (field (name "PUBLISHER") "Texas Instruments")
      )
      (libsource (lib "Resistor_0402") (part "CRCW04020000Z0ED"))
    )
    (comp (ref "R247")
      (value "CRCW04020000Z0ED")
      (footprint "0402")
      (description "RES, 0, 5%, 0.063 W, 0402")
      (fields
        (field (name "VALUEDISPLAYED") "0")
        (field (name "MANUFACTURER") "Vishay-Dale")
        (field (name "PUBLISHER") "Texas Instruments")
      )
      (libsource (lib "Resistor_0402") (part "CRCW04020000Z0ED"))
    )
    (comp (ref "R248")
      (value "CRCW04020000Z0ED")
      (footprint "0402")
      (description "RES, 0, 5%, 0.063 W, 0402")
      (fields
        (field (name "VALUEDISPLAYED") "0")
        (field (name "MANUFACTURER") "Vishay-Dale")
        (field (name "PUBLISHER") "Texas Instruments")
      )
      (libsource (lib "Resistor_0402") (part "CRCW04020000Z0ED"))
    )
    (comp (ref "R249")
      (value "CRCW04020000Z0ED")
      (footprint "0402")
      (description "RES, 0, 5%, 0.063 W, 0402")
      (fields
        (field (name "VALUEDISPLAYED") "0")
        (field (name "MANUFACTURER") "Vishay-Dale")
        (field (name "PUBLISHER") "Texas Instruments")
      )
      (libsource (lib "Resistor_0402") (part "CRCW04020000Z0ED"))
    )
    (comp (ref "R250")
      (value "CRCW04020000Z0ED")
      (footprint "0402")
      (description "RES, 0, 5%, 0.063 W, 0402")
      (fields
        (field (name "VALUEDISPLAYED") "0")
        (field (name "MANUFACTURER") "Vishay-Dale")
        (field (name "PUBLISHER") "Texas Instruments")
      )
      (libsource (lib "Resistor_0402") (part "CRCW04020000Z0ED"))
    )
    (comp (ref "R251")
      (value "CRCW04020000Z0ED")
      (footprint "0402")
      (description "RES, 0, 5%, 0.063 W, 0402")
      (fields
        (field (name "VALUEDISPLAYED") "0")
        (field (name "MANUFACTURER") "Vishay-Dale")
        (field (name "PUBLISHER") "Texas Instruments")
      )
      (libsource (lib "Resistor_0402") (part "CRCW04020000Z0ED"))
    )
    (comp (ref "R252")
      (value "CRCW04020000Z0ED")
      (footprint "0402")
      (description "RES, 0, 5%, 0.063 W, 0402")
      (fields
        (field (name "VALUEDISPLAYED") "0")
        (field (name "MANUFACTURER") "Vishay-Dale")
        (field (name "PUBLISHER") "Texas Instruments")
      )
      (libsource (lib "Resistor_0402") (part "CRCW04020000Z0ED"))
    )
    (comp (ref "R253")
      (value "CRCW04020000Z0ED")
      (footprint "0402")
      (description "RES, 0, 5%, 0.063 W, 0402")
      (fields
        (field (name "VALUEDISPLAYED") "0")
        (field (name "MANUFACTURER") "Vishay-Dale")
        (field (name "PUBLISHER") "Texas Instruments")
      )
      (libsource (lib "Resistor_0402") (part "CRCW04020000Z0ED"))
    )
    (comp (ref "R254")
      (value "CRCW04020000Z0ED")
      (footprint "0402")
      (description "RES, 0, 5%, 0.063 W, 0402")
      (fields
        (field (name "VALUEDISPLAYED") "0")
        (field (name "MANUFACTURER") "Vishay-Dale")
        (field (name "PUBLISHER") "Texas Instruments")
      )
      (libsource (lib "Resistor_0402") (part "CRCW04020000Z0ED"))
    )
    (comp (ref "R255")
      (value "CRCW04020000Z0ED")
      (footprint "0402")
      (description "RES, 0, 5%, 0.063 W, 0402")
      (fields
        (field (name "VALUEDISPLAYED") "0")
        (field (name "MANUFACTURER") "Vishay-Dale")
        (field (name "PUBLISHER") "Texas Instruments")
      )
      (libsource (lib "Resistor_0402") (part "CRCW04020000Z0ED"))
    )
    (comp (ref "R256")
      (value "CRCW04020000Z0ED")
      (footprint "0402")
      (description "RES, 0, 5%, 0.063 W, 0402")
      (fields
        (field (name "VALUEDISPLAYED") "0")
        (field (name "MANUFACTURER") "Vishay-Dale")
        (field (name "PUBLISHER") "Texas Instruments")
      )
      (libsource (lib "Resistor_0402") (part "CRCW04020000Z0ED"))
    )
    (comp (ref "R257")
      (value "CRCW04020000Z0ED")
      (footprint "0402")
      (description "RES, 0, 5%, 0.063 W, 0402")
      (fields
        (field (name "VALUEDISPLAYED") "0")
        (field (name "MANUFACTURER") "Vishay-Dale")
        (field (name "PUBLISHER") "Texas Instruments")
      )
      (libsource (lib "Resistor_0402") (part "CRCW04020000Z0ED"))
    )
    (comp (ref "R258")
      (value "CRCW040210K0FKED")
      (footprint "0402")
      (description "RES, 10.0 k, 1%, 0.063 W, 0402")
      (fields
        (field (name "VALUEDISPLAYED") "10.0k")
        (field (name "MANUFACTURER") "Vishay-Dale")
        (field (name "PUBLISHER") "Texas Instruments")
      )
      (libsource (lib "Resistor_0402") (part "CRCW040210K0FKED"))
    )
    (comp (ref "R259")
      (value "CRCW040210K0FKED")
      (footprint "0402")
      (description "RES, 10.0 k, 1%, 0.063 W, 0402")
      (fields
        (field (name "VALUEDISPLAYED") "10.0k")
        (field (name "MANUFACTURER") "Vishay-Dale")
        (field (name "PUBLISHER") "Texas Instruments")
      )
      (libsource (lib "Resistor_0402") (part "CRCW040210K0FKED"))
    )
    (comp (ref "R260")
      (value "ERJ-3EKF1302V")
      (footprint "0603")
      (description "RES, 13 k, 0.1%, 0.1 W, 0603")
      (fields
        (field (name "MANUFACTURER") "Yageo America")
        (field (name "VALUEDISPLAYED") "13k")
        (field (name "PUBLISHER") "Texas Instruments")
      )
      (libsource (lib "TIDA-010086") (part "Resistor"))
    )
    (comp (ref "R261")
      (value "CRCW04020000Z0ED")
      (footprint "0402")
      (description "RES, 0, 5%, 0.063 W, 0402")
      (fields
        (field (name "VALUEDISPLAYED") "0")
        (field (name "MANUFACTURER") "Vishay-Dale")
        (field (name "PUBLISHER") "Texas Instruments")
      )
      (libsource (lib "Resistor_0402") (part "CRCW04020000Z0ED"))
    )
    (comp (ref "R262")
      (value "CRCW04020000Z0ED")
      (footprint "0402")
      (description "RES, 0, 5%, 0.063 W, 0402")
      (fields
        (field (name "VALUEDISPLAYED") "0")
        (field (name "MANUFACTURER") "Vishay-Dale")
        (field (name "PUBLISHER") "Texas Instruments")
      )
      (libsource (lib "Resistor_0402") (part "CRCW04020000Z0ED"))
    )
    (comp (ref "R263")
      (value "CRCW04020000Z0ED")
      (footprint "0402")
      (description "RES, 0, 5%, 0.063 W, 0402")
      (fields
        (field (name "VALUEDISPLAYED") "0")
        (field (name "MANUFACTURER") "Vishay-Dale")
        (field (name "PUBLISHER") "Texas Instruments")
      )
      (libsource (lib "Resistor_0402") (part "CRCW04020000Z0ED"))
    )
    (comp (ref "R264")
      (value "CRCW04020000Z0ED")
      (footprint "0402")
      (description "RES, 0, 5%, 0.063 W, 0402")
      (fields
        (field (name "VALUEDISPLAYED") "0")
        (field (name "MANUFACTURER") "Vishay-Dale")
        (field (name "PUBLISHER") "Texas Instruments")
      )
      (libsource (lib "Resistor_0402") (part "CRCW04020000Z0ED"))
    )
    (comp (ref "R265")
      (value "CRCW04020000Z0ED")
      (footprint "0402")
      (description "RES, 0, 5%, 0.063 W, 0402")
      (fields
        (field (name "VALUEDISPLAYED") "0")
        (field (name "MANUFACTURER") "Vishay-Dale")
        (field (name "PUBLISHER") "Texas Instruments")
      )
      (libsource (lib "Resistor_0402") (part "CRCW04020000Z0ED"))
    )
    (comp (ref "R266")
      (value "CRCW04020000Z0ED")
      (footprint "0402")
      (description "RES, 0, 5%, 0.063 W, 0402")
      (fields
        (field (name "VALUEDISPLAYED") "0")
        (field (name "MANUFACTURER") "Vishay-Dale")
        (field (name "PUBLISHER") "Texas Instruments")
      )
      (libsource (lib "Resistor_0402") (part "CRCW04020000Z0ED"))
    )
    (comp (ref "R267")
      (value "CRCW04020000Z0ED")
      (footprint "0402")
      (description "RES, 0, 5%, 0.063 W, 0402")
      (fields
        (field (name "VALUEDISPLAYED") "0")
        (field (name "MANUFACTURER") "Vishay-Dale")
        (field (name "PUBLISHER") "Texas Instruments")
      )
      (libsource (lib "Resistor_0402") (part "CRCW04020000Z0ED"))
    )
    (comp (ref "R268")
      (value "CRCW04020000Z0ED")
      (footprint "0402")
      (description "RES, 0, 5%, 0.063 W, 0402")
      (fields
        (field (name "VALUEDISPLAYED") "0")
        (field (name "MANUFACTURER") "Vishay-Dale")
        (field (name "PUBLISHER") "Texas Instruments")
      )
      (libsource (lib "Resistor_0402") (part "CRCW04020000Z0ED"))
    )
    (comp (ref "R269")
      (value "CRCW04020000Z0ED")
      (footprint "0402")
      (description "RES, 0, 5%, 0.063 W, 0402")
      (fields
        (field (name "VALUEDISPLAYED") "0")
        (field (name "MANUFACTURER") "Vishay-Dale")
        (field (name "PUBLISHER") "Texas Instruments")
      )
      (libsource (lib "Resistor_0402") (part "CRCW04020000Z0ED"))
    )
    (comp (ref "R270")
      (value "CRCW04020000Z0ED")
      (footprint "0402")
      (description "RES, 0, 5%, 0.063 W, 0402")
      (fields
        (field (name "VALUEDISPLAYED") "0")
        (field (name "MANUFACTURER") "Vishay-Dale")
        (field (name "PUBLISHER") "Texas Instruments")
      )
      (libsource (lib "Resistor_0402") (part "CRCW04020000Z0ED"))
    )
    (comp (ref "R271")
      (value "CRCW04020000Z0ED")
      (footprint "0402")
      (description "RES, 0, 5%, 0.063 W, 0402")
      (fields
        (field (name "VALUEDISPLAYED") "0")
        (field (name "MANUFACTURER") "Vishay-Dale")
        (field (name "PUBLISHER") "Texas Instruments")
      )
      (libsource (lib "Resistor_0402") (part "CRCW04020000Z0ED"))
    )
    (comp (ref "R272")
      (value "CRCW04020000Z0ED")
      (footprint "0402")
      (description "RES, 0, 5%, 0.063 W, 0402")
      (fields
        (field (name "VALUEDISPLAYED") "0")
        (field (name "MANUFACTURER") "Vishay-Dale")
        (field (name "PUBLISHER") "Texas Instruments")
      )
      (libsource (lib "Resistor_0402") (part "CRCW04020000Z0ED"))
    )
    (comp (ref "R273")
      (value "CRCW04020000Z0ED")
      (footprint "0402")
      (description "RES, 0, 5%, 0.063 W, 0402")
      (fields
        (field (name "VALUEDISPLAYED") "0")
        (field (name "MANUFACTURER") "Vishay-Dale")
        (field (name "PUBLISHER") "Texas Instruments")
      )
      (libsource (lib "Resistor_0402") (part "CRCW04020000Z0ED"))
    )
    (comp (ref "R274")
      (value "CRCW04020000Z0ED")
      (footprint "0402")
      (description "RES, 0, 5%, 0.063 W, 0402")
      (fields
        (field (name "VALUEDISPLAYED") "0")
        (field (name "MANUFACTURER") "Vishay-Dale")
        (field (name "PUBLISHER") "Texas Instruments")
      )
      (libsource (lib "Resistor_0402") (part "CRCW04020000Z0ED"))
    )
    (comp (ref "R275")
      (value "CRCW04020000Z0ED")
      (footprint "0402")
      (description "RES, 0, 5%, 0.063 W, 0402")
      (fields
        (field (name "VALUEDISPLAYED") "0")
        (field (name "MANUFACTURER") "Vishay-Dale")
        (field (name "PUBLISHER") "Texas Instruments")
      )
      (libsource (lib "Resistor_0402") (part "CRCW04020000Z0ED"))
    )
    (comp (ref "R276")
      (value "CRCW04020000Z0ED")
      (footprint "0402")
      (description "RES, 0, 5%, 0.063 W, 0402")
      (fields
        (field (name "VALUEDISPLAYED") "0")
        (field (name "MANUFACTURER") "Vishay-Dale")
        (field (name "PUBLISHER") "Texas Instruments")
      )
      (libsource (lib "Resistor_0402") (part "CRCW04020000Z0ED"))
    )
    (comp (ref "R277")
      (value "FC0402E50R0BST1")
      (footprint "0402")
      (description "RES, 50, 0.1%, 0.05 W, 0402")
      (fields
        (field (name "VALUEDISPLAYED") "50")
        (field (name "MANUFACTURER") "Vishay-Dale")
        (field (name "PUBLISHER") "Texas Instruments")
      )
      (libsource (lib "Resistor_0402") (part "FC0402E50R0BST1"))
    )
    (comp (ref "R278")
      (value "CRCW04020000Z0ED")
      (footprint "0402")
      (description "RES, 0, 5%, 0.063 W, 0402")
      (fields
        (field (name "VALUEDISPLAYED") "0")
        (field (name "MANUFACTURER") "Vishay-Dale")
        (field (name "PUBLISHER") "Texas Instruments")
      )
      (libsource (lib "Resistor_0402") (part "CRCW04020000Z0ED"))
    )
    (comp (ref "R279")
      (value "FC0402E50R0BST1")
      (footprint "0402")
      (description "RES, 50, 0.1%, 0.05 W, 0402")
      (fields
        (field (name "VALUEDISPLAYED") "50")
        (field (name "MANUFACTURER") "Vishay-Dale")
        (field (name "PUBLISHER") "Texas Instruments")
      )
      (libsource (lib "Resistor_0402") (part "FC0402E50R0BST1"))
    )
    (comp (ref "R280")
      (value "FC0402E50R0BST1")
      (footprint "0402")
      (description "RES, 50, 0.1%, 0.05 W, 0402")
      (fields
        (field (name "VALUEDISPLAYED") "50")
        (field (name "MANUFACTURER") "Vishay-Dale")
        (field (name "PUBLISHER") "Texas Instruments")
      )
      (libsource (lib "Resistor_0402") (part "FC0402E50R0BST1"))
    )
    (comp (ref "R281")
      (value "CRCW04020000Z0ED")
      (footprint "0402")
      (description "RES, 0, 5%, 0.063 W, 0402")
      (fields
        (field (name "VALUEDISPLAYED") "0")
        (field (name "MANUFACTURER") "Vishay-Dale")
        (field (name "PUBLISHER") "Texas Instruments")
      )
      (libsource (lib "Resistor_0402") (part "CRCW04020000Z0ED"))
    )
    (comp (ref "R282")
      (value "FC0402E50R0BST1")
      (footprint "0402")
      (description "RES, 50, 0.1%, 0.05 W, 0402")
      (fields
        (field (name "VALUEDISPLAYED") "50")
        (field (name "MANUFACTURER") "Vishay-Dale")
        (field (name "PUBLISHER") "Texas Instruments")
      )
      (libsource (lib "Resistor_0402") (part "FC0402E50R0BST1"))
    )
    (comp (ref "R283")
      (value "CRCW04020000Z0ED")
      (footprint "0402")
      (description "RES, 0, 5%, 0.063 W, 0402")
      (fields
        (field (name "VALUEDISPLAYED") "0")
        (field (name "MANUFACTURER") "Vishay-Dale")
        (field (name "PUBLISHER") "Texas Instruments")
      )
      (libsource (lib "Resistor_0402") (part "CRCW04020000Z0ED"))
    )
    (comp (ref "R284")
      (value "FC0402E50R0BST1")
      (footprint "0402")
      (description "RES, 50, 0.1%, 0.05 W, 0402")
      (fields
        (field (name "VALUEDISPLAYED") "50")
        (field (name "MANUFACTURER") "Vishay-Dale")
        (field (name "PUBLISHER") "Texas Instruments")
      )
      (libsource (lib "Resistor_0402") (part "FC0402E50R0BST1"))
    )
    (comp (ref "R285")
      (value "FC0402E50R0BST1")
      (footprint "0402")
      (description "RES, 50, 0.1%, 0.05 W, 0402")
      (fields
        (field (name "VALUEDISPLAYED") "50")
        (field (name "MANUFACTURER") "Vishay-Dale")
        (field (name "PUBLISHER") "Texas Instruments")
      )
      (libsource (lib "Resistor_0402") (part "FC0402E50R0BST1"))
    )
    (comp (ref "R286")
      (value "FC0402E50R0BST1")
      (footprint "0402")
      (description "RES, 50, 0.1%, 0.05 W, 0402")
      (fields
        (field (name "VALUEDISPLAYED") "50")
        (field (name "MANUFACTURER") "Vishay-Dale")
        (field (name "PUBLISHER") "Texas Instruments")
      )
      (libsource (lib "Resistor_0402") (part "FC0402E50R0BST1"))
    )
    (comp (ref "R288")
      (value "FC0402E50R0BST1")
      (footprint "0402")
      (description "RES, 50, 0.1%, 0.05 W, 0402")
      (fields
        (field (name "VALUEDISPLAYED") "50")
        (field (name "MANUFACTURER") "Vishay-Dale")
        (field (name "PUBLISHER") "Texas Instruments")
      )
      (libsource (lib "Resistor_0402") (part "FC0402E50R0BST1"))
    )
    (comp (ref "R289")
      (value "CRCW04020000Z0ED")
      (footprint "0402")
      (description "RES, 0, 5%, 0.063 W, 0402")
      (fields
        (field (name "VALUEDISPLAYED") "0")
        (field (name "MANUFACTURER") "Vishay-Dale")
        (field (name "PUBLISHER") "Texas Instruments")
      )
      (libsource (lib "Resistor_0402") (part "CRCW04020000Z0ED"))
    )
    (comp (ref "R292")
      (value "FC0402E50R0BST1")
      (footprint "0402")
      (description "RES, 50, 0.1%, 0.05 W, 0402")
      (fields
        (field (name "VALUEDISPLAYED") "50")
        (field (name "MANUFACTURER") "Vishay-Dale")
        (field (name "PUBLISHER") "Texas Instruments")
      )
      (libsource (lib "Resistor_0402") (part "FC0402E50R0BST1"))
    )
    (comp (ref "R293")
      (value "CRCW04020000Z0ED")
      (footprint "0402")
      (description "RES, 0, 5%, 0.063 W, 0402")
      (fields
        (field (name "VALUEDISPLAYED") "0")
        (field (name "MANUFACTURER") "Vishay-Dale")
        (field (name "PUBLISHER") "Texas Instruments")
      )
      (libsource (lib "Resistor_0402") (part "CRCW04020000Z0ED"))
    )
    (comp (ref "R294")
      (value "CRCW04020000Z0ED")
      (footprint "0402")
      (description "RES, 0, 5%, 0.063 W, 0402")
      (fields
        (field (name "VALUEDISPLAYED") "0")
        (field (name "MANUFACTURER") "Vishay-Dale")
        (field (name "PUBLISHER") "Texas Instruments")
      )
      (libsource (lib "Resistor_0402") (part "CRCW04020000Z0ED"))
    )
    (comp (ref "R295")
      (value "CRCW04020000Z0ED")
      (footprint "0402")
      (description "RES, 0, 5%, 0.063 W, 0402")
      (fields
        (field (name "VALUEDISPLAYED") "0")
        (field (name "MANUFACTURER") "Vishay-Dale")
        (field (name "PUBLISHER") "Texas Instruments")
      )
      (libsource (lib "Resistor_0402") (part "CRCW04020000Z0ED"))
    )
    (comp (ref "R296")
      (value "CRCW04020000Z0ED")
      (footprint "0402")
      (description "RES, 0, 5%, 0.063 W, 0402")
      (fields
        (field (name "VALUEDISPLAYED") "0")
        (field (name "MANUFACTURER") "Vishay-Dale")
        (field (name "PUBLISHER") "Texas Instruments")
      )
      (libsource (lib "Resistor_0402") (part "CRCW04020000Z0ED"))
    )
    (comp (ref "R297")
      (value "CRCW04020000Z0ED")
      (footprint "0402")
      (description "RES, 0, 5%, 0.063 W, 0402")
      (fields
        (field (name "VALUEDISPLAYED") "0")
        (field (name "MANUFACTURER") "Vishay-Dale")
        (field (name "PUBLISHER") "Texas Instruments")
      )
      (libsource (lib "Resistor_0402") (part "CRCW04020000Z0ED"))
    )
    (comp (ref "R298")
      (value "FC0402E50R0BST1")
      (footprint "0402")
      (description "RES, 50, 0.1%, 0.05 W, 0402")
      (fields
        (field (name "VALUEDISPLAYED") "50")
        (field (name "MANUFACTURER") "Vishay-Dale")
        (field (name "PUBLISHER") "Texas Instruments")
      )
      (libsource (lib "Resistor_0402") (part "FC0402E50R0BST1"))
    )
    (comp (ref "R299")
      (value "RG1608P-8062-B-T5")
      (footprint "0603")
      (description "RES, 80.6 k, 0.1%, 0.1 W, 0603")
      (fields
        (field (name "MANUFACTURER") "Yageo America")
        (field (name "VALUEDISPLAYED") "80.6k")
        (field (name "PUBLISHER") "Texas Instruments")
      )
      (libsource (lib "TIDA-010086") (part "Resistor"))
    )
    (comp (ref "R300")
      (value "CRCW04020000Z0ED")
      (footprint "0402")
      (description "RES, 0, 5%, 0.063 W, 0402")
      (fields
        (field (name "VALUEDISPLAYED") "0")
        (field (name "MANUFACTURER") "Vishay-Dale")
        (field (name "PUBLISHER") "Texas Instruments")
      )
      (libsource (lib "Resistor_0402") (part "CRCW04020000Z0ED"))
    )
    (comp (ref "R301")
      (value "RG1608P-8062-B-T5")
      (footprint "0603")
      (description "RES, 80.6 k, 0.1%, 0.1 W, 0603")
      (fields
        (field (name "MANUFACTURER") "Yageo America")
        (field (name "VALUEDISPLAYED") "80.6k")
        (field (name "PUBLISHER") "Texas Instruments")
      )
      (libsource (lib "TIDA-010086") (part "Resistor"))
    )
    (comp (ref "R303")
      (value "ERJ-3EKF1302V")
      (footprint "0603")
      (description "RES, 13 k, 0.1%, 0.1 W, 0603")
      (fields
        (field (name "MANUFACTURER") "Yageo America")
        (field (name "VALUEDISPLAYED") "13k")
        (field (name "PUBLISHER") "Texas Instruments")
      )
      (libsource (lib "TIDA-010086") (part "Resistor"))
    )
    (comp (ref "R306")
      (value "RC0603FR-07100KL")
      (footprint "0603")
      (description "RES, 100 k, 1%, 0.1 W, 0603")
      (fields (field (name "MANUFACTURER") "Yageo") (field (name "VALUEDISPLAYED") "100k"))
      (libsource (lib "TIDA-010086") (part "Resistor"))
    )
    (comp (ref "R307")
      (value "RC0603FR-07100KL")
      (footprint "0603")
      (description "RES, 100 k, 1%, 0.1 W, 0603")
      (fields (field (name "MANUFACTURER") "Yageo") (field (name "VALUEDISPLAYED") "100k"))
      (libsource (lib "TIDA-010086") (part "Resistor"))
    )
    (comp (ref "R308")
      (value "RC0603FR-07100KL")
      (footprint "0603")
      (description "RES, 100 k, 1%, 0.1 W, 0603")
      (fields (field (name "MANUFACTURER") "Yageo") (field (name "VALUEDISPLAYED") "100k"))
      (libsource (lib "TIDA-010086") (part "Resistor"))
    )
    (comp (ref "R309")
      (value "RC0603FR-07100KL")
      (footprint "0603")
      (description "RES, 100 k, 1%, 0.1 W, 0603")
      (fields (field (name "MANUFACTURER") "Yageo") (field (name "VALUEDISPLAYED") "100k"))
      (libsource (lib "TIDA-010086") (part "Resistor"))
    )
    (comp (ref "R310")
      (value "CRCW04020000Z0ED")
      (footprint "0402")
      (description "RES, 0, 5%, 0.063 W, 0402")
      (fields
        (field (name "VALUEDISPLAYED") "0")
        (field (name "MANUFACTURER") "Vishay-Dale")
        (field (name "PUBLISHER") "Texas Instruments")
      )
      (libsource (lib "Resistor_0402") (part "CRCW04020000Z0ED"))
    )
    (comp (ref "R311")
      (value "CRCW04020000Z0ED")
      (footprint "0402")
      (description "RES, 0, 5%, 0.063 W, 0402")
      (fields
        (field (name "VALUEDISPLAYED") "0")
        (field (name "MANUFACTURER") "Vishay-Dale")
        (field (name "PUBLISHER") "Texas Instruments")
      )
      (libsource (lib "Resistor_0402") (part "CRCW04020000Z0ED"))
    )
    (comp (ref "R312")
      (value "FC0402E50R0BST1")
      (footprint "0402")
      (description "RES, 50, 0.1%, 0.05 W, 0402")
      (fields
        (field (name "VALUEDISPLAYED") "50")
        (field (name "MANUFACTURER") "Vishay-Dale")
        (field (name "PUBLISHER") "Texas Instruments")
      )
      (libsource (lib "Resistor_0402") (part "FC0402E50R0BST1"))
    )
    (comp (ref "R313")
      (value "CRCW04020000Z0ED")
      (footprint "0402")
      (description "RES, 0, 5%, 0.063 W, 0402")
      (fields
        (field (name "VALUEDISPLAYED") "0")
        (field (name "MANUFACTURER") "Vishay-Dale")
        (field (name "PUBLISHER") "Texas Instruments")
      )
      (libsource (lib "Resistor_0402") (part "CRCW04020000Z0ED"))
    )
    (comp (ref "R314")
      (value "CRCW04020000Z0ED")
      (footprint "0402")
      (description "RES, 0, 5%, 0.063 W, 0402")
      (fields
        (field (name "VALUEDISPLAYED") "0")
        (field (name "MANUFACTURER") "Vishay-Dale")
        (field (name "PUBLISHER") "Texas Instruments")
      )
      (libsource (lib "Resistor_0402") (part "CRCW04020000Z0ED"))
    )
    (comp (ref "R315")
      (value "CRCW04020000Z0ED")
      (footprint "0402")
      (description "RES, 0, 5%, 0.063 W, 0402")
      (fields
        (field (name "VALUEDISPLAYED") "0")
        (field (name "MANUFACTURER") "Vishay-Dale")
        (field (name "PUBLISHER") "Texas Instruments")
      )
      (libsource (lib "Resistor_0402") (part "CRCW04020000Z0ED"))
    )
    (comp (ref "R316")
      (value "CRCW06034K99FKEA")
      (footprint "0603L")
      (description "RES, 4.99 k, 1%, 0.1 W, 0603")
      (fields
        (field (name "VALUEDISPLAYED") "4.99k")
        (field (name "MANUFACTURER") "Vishay-Dale")
        (field (name "PUBLISHER") "Texas Instruments")
      )
      (libsource (lib "Resistor_0603") (part "CRCW06034K99FKEA"))
    )
    (comp (ref "R317")
      (value "RC0603FR-07100KL")
      (footprint "0603")
      (description "RES, 100 k, 1%, 0.1 W, 0603")
      (fields (field (name "MANUFACTURER") "Yageo") (field (name "VALUEDISPLAYED") "100k"))
      (libsource (lib "TIDA-010086") (part "Resistor"))
    )
    (comp (ref "R318")
      (value "RC0603FR-07100KL")
      (footprint "0603")
      (description "RES, 100 k, 1%, 0.1 W, 0603")
      (fields (field (name "MANUFACTURER") "Yageo") (field (name "VALUEDISPLAYED") "100k"))
      (libsource (lib "TIDA-010086") (part "Resistor"))
    )
    (comp (ref "R319")
      (value "RT0603BRD07100KL")
      (footprint "0603")
      (description "RES, 100 k, 0.1%, 0.1 W, 0603")
      (fields
        (field (name "MANUFACTURER") "Yageo America")
        (field (name "VALUEDISPLAYED") "100k")
        (field (name "PUBLISHER") "Texas Instruments")
      )
      (libsource (lib "TIDA-010086") (part "Resistor"))
    )
    (comp (ref "R320")
      (value "CRCW060349K9FKEA")
      (footprint "0603")
      (description "RES, 49.9 k, 1%, 0.1 W, 0603")
      (fields
        (field (name "VALUEDISPLAYED") "49.9k")
        (field (name "MANUFACTURER") "Vishay-Dale")
        (field (name "PUBLISHER") "Texas Instruments")
      )
      (libsource (lib "Resistor_0603") (part "CRCW060349K9FKEA"))
    )
    (comp (ref "R321")
      (value "RT0603BRD07100KL")
      (footprint "0603")
      (description "RES, 100 k, 0.1%, 0.1 W, 0603")
      (fields
        (field (name "MANUFACTURER") "Yageo America")
        (field (name "VALUEDISPLAYED") "100k")
        (field (name "PUBLISHER") "Texas Instruments")
      )
      (libsource (lib "TIDA-010086") (part "Resistor"))
    )
    (comp (ref "R322")
      (value "CRCW060349K9FKEA")
      (footprint "0603")
      (description "RES, 49.9 k, 1%, 0.1 W, 0603")
      (fields
        (field (name "VALUEDISPLAYED") "49.9k")
        (field (name "MANUFACTURER") "Vishay-Dale")
        (field (name "PUBLISHER") "Texas Instruments")
      )
      (libsource (lib "Resistor_0603") (part "CRCW060349K9FKEA"))
    )
    (comp (ref "R323")
      (value "RT0603BRD07100KL")
      (footprint "0603")
      (description "RES, 100 k, 0.1%, 0.1 W, 0603")
      (fields
        (field (name "MANUFACTURER") "Yageo America")
        (field (name "VALUEDISPLAYED") "100k")
        (field (name "PUBLISHER") "Texas Instruments")
      )
      (libsource (lib "TIDA-010086") (part "Resistor"))
    )
    (comp (ref "R324")
      (value "CRCW060349K9FKEA")
      (footprint "0603")
      (description "RES, 49.9 k, 1%, 0.1 W, 0603")
      (fields
        (field (name "VALUEDISPLAYED") "49.9k")
        (field (name "MANUFACTURER") "Vishay-Dale")
        (field (name "PUBLISHER") "Texas Instruments")
      )
      (libsource (lib "Resistor_0603") (part "CRCW060349K9FKEA"))
    )
    (comp (ref "R325")
      (value "RT0603BRD07100KL")
      (footprint "0603")
      (description "RES, 100 k, 0.1%, 0.1 W, 0603")
      (fields
        (field (name "MANUFACTURER") "Yageo America")
        (field (name "VALUEDISPLAYED") "100k")
        (field (name "PUBLISHER") "Texas Instruments")
      )
      (libsource (lib "TIDA-010086") (part "Resistor"))
    )
    (comp (ref "R326")
      (value "CRCW060349K9FKEA")
      (footprint "0603")
      (description "RES, 49.9 k, 1%, 0.1 W, 0603")
      (fields
        (field (name "VALUEDISPLAYED") "49.9k")
        (field (name "MANUFACTURER") "Vishay-Dale")
        (field (name "PUBLISHER") "Texas Instruments")
      )
      (libsource (lib "Resistor_0603") (part "CRCW060349K9FKEA"))
    )
    (comp (ref "R327")
      (value "RT0603BRD07100KL")
      (footprint "0603")
      (description "RES, 100 k, 0.1%, 0.1 W, 0603")
      (fields
        (field (name "MANUFACTURER") "Yageo America")
        (field (name "VALUEDISPLAYED") "100k")
        (field (name "PUBLISHER") "Texas Instruments")
      )
      (libsource (lib "TIDA-010086") (part "Resistor"))
    )
    (comp (ref "R328")
      (value "RT0603BRD07100KL")
      (footprint "0603")
      (description "RES, 100 k, 0.1%, 0.1 W, 0603")
      (fields
        (field (name "MANUFACTURER") "Yageo America")
        (field (name "VALUEDISPLAYED") "100k")
        (field (name "PUBLISHER") "Texas Instruments")
      )
      (libsource (lib "TIDA-010086") (part "Resistor"))
    )
    (comp (ref "R329")
      (value "CRCW060349K9FKEA")
      (footprint "0603")
      (description "RES, 49.9 k, 1%, 0.1 W, 0603")
      (fields
        (field (name "VALUEDISPLAYED") "49.9k")
        (field (name "MANUFACTURER") "Vishay-Dale")
        (field (name "PUBLISHER") "Texas Instruments")
      )
      (libsource (lib "Resistor_0603") (part "CRCW060349K9FKEA"))
    )
    (comp (ref "R330")
      (value "RT0603BRD07100KL")
      (footprint "0603")
      (description "RES, 100 k, 0.1%, 0.1 W, 0603")
      (fields
        (field (name "MANUFACTURER") "Yageo America")
        (field (name "VALUEDISPLAYED") "100k")
        (field (name "PUBLISHER") "Texas Instruments")
      )
      (libsource (lib "TIDA-010086") (part "Resistor"))
    )
    (comp (ref "R331")
      (value "CRCW060349K9FKEA")
      (footprint "0603")
      (description "RES, 49.9 k, 1%, 0.1 W, 0603")
      (fields
        (field (name "VALUEDISPLAYED") "49.9k")
        (field (name "MANUFACTURER") "Vishay-Dale")
        (field (name "PUBLISHER") "Texas Instruments")
      )
      (libsource (lib "Resistor_0603") (part "CRCW060349K9FKEA"))
    )
    (comp (ref "R332")
      (value "RT0603BRD07100KL")
      (footprint "0603")
      (description "RES, 100 k, 0.1%, 0.1 W, 0603")
      (fields
        (field (name "MANUFACTURER") "Yageo America")
        (field (name "VALUEDISPLAYED") "100k")
        (field (name "PUBLISHER") "Texas Instruments")
      )
      (libsource (lib "TIDA-010086") (part "Resistor"))
    )
    (comp (ref "R333")
      (value "CRCW060349K9FKEA")
      (footprint "0603")
      (description "RES, 49.9 k, 1%, 0.1 W, 0603")
      (fields
        (field (name "VALUEDISPLAYED") "49.9k")
        (field (name "MANUFACTURER") "Vishay-Dale")
        (field (name "PUBLISHER") "Texas Instruments")
      )
      (libsource (lib "Resistor_0603") (part "CRCW060349K9FKEA"))
    )
    (comp (ref "R334")
      (value "RT0603BRD07100KL")
      (footprint "0603")
      (description "RES, 100 k, 0.1%, 0.1 W, 0603")
      (fields
        (field (name "MANUFACTURER") "Yageo America")
        (field (name "VALUEDISPLAYED") "100k")
        (field (name "PUBLISHER") "Texas Instruments")
      )
      (libsource (lib "TIDA-010086") (part "Resistor"))
    )
    (comp (ref "R335")
      (value "CRCW060349K9FKEA")
      (footprint "0603")
      (description "RES, 49.9 k, 1%, 0.1 W, 0603")
      (fields
        (field (name "VALUEDISPLAYED") "49.9k")
        (field (name "MANUFACTURER") "Vishay-Dale")
        (field (name "PUBLISHER") "Texas Instruments")
      )
      (libsource (lib "Resistor_0603") (part "CRCW060349K9FKEA"))
    )
    (comp (ref "S4")
      (value "218-8LPST")
      (footprint "SW_218-8LP")
      (description "Switch, SPST, 8 Pos, 25mA, 24VDC, SMD")
      (fields
        (field (name "MANUFACTURER") "CTS Electrocomponents")
        (field (name "PUBLISHER") "Texas Instruments")
      )
      (libsource (lib "TIDA-010086") (part "SW_8SPST"))
    )
    (comp (ref "S5")
      (value "218-8LPST")
      (footprint "SW_218-8LP")
      (description "Switch, SPST, 8 Pos, 25mA, 24VDC, SMD")
      (fields
        (field (name "MANUFACTURER") "CTS Electrocomponents")
        (field (name "PUBLISHER") "Texas Instruments")
      )
      (libsource (lib "TIDA-010086") (part "SW_8SPST"))
    )
    (comp (ref "S6")
      (value "Switch_PushButton")
      (footprint "SW_TL1015AF160QG")
      (description "Switch, Tactile, SPST-NO, 0.05A, 12V, SMT")
      (fields
        (field (name "PARTNUMBER") "TL1015AF160QG")
        (field (name "MANUFACTURER") "E-Switch")
        (field (name "PUBLISHER") "Texas Instruments")
      )
      (libsource (lib "TIDA-010086") (part "Switch_PushButton"))
    )
    (comp (ref "TP41")
      (value "5001")
      (footprint "Keystone5001")
      (description "Test Point, Miniature, Black, TH")
      (fields (field (name "MANUFACTURER") "Keystone") (field (name "PUBLISHER") "Texas Instruments"))
      (libsource (lib "Connectors_Keystone") (part "5001"))
    )
    (comp (ref "U14")
      (value "TLV171IDBVR")
      (footprint "DBV0005A_N")
      (description "36V, Low-Power, RRO, General-Purpose Operational Amplifier, DBV0005A (SOT-23-5)")
      (fields
        (field (name "ALTERNATE PARTNUMBER") "TLV171IDBVT")
        (field (name "MANUFACTURER") "Texas Instruments")
        (field (name "PARTNUMBER") "TLV171IDBVR")
        (field (name "PUBLISHER") "Texas Instruments")
      )
      (libsource (lib "TIDA-010086") (part "OpAmp_Single_SOTSTD"))
    )
    (comp (ref "U17")
      (value "CC3220MODA")
      (footprint "CC3220MODASF12MONR")
      (description "CC3220MODASF12MONR - IC RF TxRx + MCU WiFi 802.11b/g/n 2.4GHz 63-SMD Module, RoHS compliant")
      (libsource (lib "Ongyi") (part "CC3220MODA"))
    )
    (comp (ref "U18")
      (value "SN74LVC2G17DBVT")
      (footprint "DBV0006A_N")
      (description "Dual Schmitt-Trigger Buffer, DBV0006A, SMALL T&R")
      (fields
        (field (name "GENERIC PART NUMBER") "SN74LVC2G17")
        (field (name "MANUFACTURER") "Texas Instruments")
      )
      (libsource (lib "TIDA-010086") (part "TI-SN74XXX2GXXX-6_A-SCHMITT"))
    )
    (comp (ref "U24")
      (value "SN74LVC08ADBR")
      (footprint "DB0014A_M")
      (description "Quadruple 2-Input Positive-AND Gate, DB0014A, LARGE T&R")
      (fields
        (field (name "MANUFACTURER") "Texas Instruments")
        (field (name "GENERIC PART NUMBER") "SN74LVC08A")
      )
      (libsource (lib "Altium Content Vault") (part "TI-AND-4-2IN-14"))
    )
    (comp (ref "U26")
      (value "SN74HC148DR")
      (footprint "D0016A-MFG")
      (description "Priority Encoder 1 x 8:3 16-SOIC")
      (fields (field (name "MANUFACTURER") "Texas Instruments") (field (name "PARTNUMBER") "SN74HC148DR"))
      (libsource (lib "TIDA-010086") (part "SYM-SN74HC148DR"))
    )
    (comp (ref "U27")
      (value "SN74HC148DR")
      (footprint "D0016A-MFG")
      (description "Priority Encoder 1 x 8:3 16-SOIC")
      (fields (field (name "MANUFACTURER") "Texas Instruments") (field (name "PARTNUMBER") "SN74HC148DR"))
      (libsource (lib "TIDA-010086") (part "SYM-SN74HC148DR"))
    )
    (comp (ref "U28")
      (value "SN74LVC08ADBR")
      (footprint "DB0014A_M")
      (description "Quadruple 2-Input Positive-AND Gate, DB0014A, LARGE T&R")
      (fields
        (field (name "MANUFACTURER") "Texas Instruments")
        (field (name "GENERIC PART NUMBER") "SN74LVC08A")
      )
      (libsource (lib "") (part "TI-AND-4-2IN-14_1"))
    )
    (comp (ref "U34")
      (value "FM24V10-G")
      (footprint "FP-51-85066-IPC_A")
      (description "IC FRAM 1M I2C 3.4MHZ 8SOIC")
      (libsource (lib "TIDA-010086") (part "d0711c86b564d86c4b230fd196adeb8"))
    )
    (comp (ref "U35")
      (value "SN65HVD234DR")
      (footprint "D0008A_M")
      (fields (field (name "MANUFACTURER") "Texas Instruments"))
      (libsource (lib "TIDA-010086") (part "TI-SN65HVD234-SOIC_D-8"))
    )
    (comp (ref "U39")
      (value "ESP32 LOLIN32 V1.0.0")
      (footprint "ESP32_LOLIN32_V1")
      (libsource (lib "TIDA-010086") (part "ESP32_WLOIN"))
    )
  )
  (nets
    (net (code "1") (name "/ADC.A1") (class "Default")
      (node (ref "J5") (pin "110") (pinfunction "110_110") (pintype "passive"))
      (node (ref "R246") (pin "2") (pinfunction "2_2") (pintype "passive"))
    )
    (net (code "2") (name "/ADC.B1") (class "Default")
      (node (ref "J5") (pin "107") (pinfunction "107_107") (pintype "passive"))
      (node (ref "R248") (pin "2") (pinfunction "2_2") (pintype "passive"))
    )
    (net (code "3") (name "/C2000_RESET2") (class "Default")
      (node (ref "C126") (pin "1") (pinfunction "1_1") (pintype "passive"))
      (node (ref "J5") (pin "1") (pinfunction "1_1") (pintype "passive"))
      (node (ref "S6") (pin "1") (pinfunction "1_1") (pintype "passive"))
    )
    (net (code "4") (name "/CC3220.Reset") (class "Default")
      (node (ref "D12") (pin "2") (pinfunction "A_2") (pintype "passive"))
      (node (ref "D13") (pin "2") (pinfunction "A_2") (pintype "passive"))
      (node (ref "R306") (pin "1") (pinfunction "1_1") (pintype "passive"))
      (node (ref "U17") (pin "35") (pinfunction "nRESET_35") (pintype "input"))
    )
    (net (code "5") (name "/CC3220_reset") (class "Default")
      (node (ref "D12") (pin "1") (pinfunction "K_1") (pintype "passive"))
    )
    (net (code "6") (name "/CLK1") (class "Default")
      (node (ref "R292") (pin "2") (pinfunction "2_2") (pintype "passive"))
    )
    (net (code "7") (name "/CLK2") (class "Default")
      (node (ref "R56") (pin "2") (pinfunction "2_2") (pintype "passive"))
    )
    (net (code "8") (name "/DRDY1") (class "Default")
      (node (ref "R272") (pin "2") (pinfunction "2_2") (pintype "passive"))
    )
    (net (code "9") (name "/DRDY2") (class "Default")
      (node (ref "R297") (pin "1") (pinfunction "1_1") (pintype "passive"))
    )
    (net (code "10") (name "/DRDY3") (class "Default")
      (node (ref "R296") (pin "2") (pinfunction "2_2") (pintype "passive"))
    )
    (net (code "11") (name "/DRDY4") (class "Default")
      (node (ref "R222") (pin "2") (pinfunction "2_2") (pintype "passive"))
    )
    (net (code "12") (name "/EN_A") (class "Default")
      (node (ref "R276") (pin "1") (pinfunction "1_1") (pintype "passive"))
      (node (ref "U26") (pin "9") (pinfunction "A0_9") (pintype "output"))
    )
    (net (code "13") (name "/EN_B") (class "Default")
      (node (ref "R283") (pin "1") (pinfunction "1_1") (pintype "passive"))
      (node (ref "U26") (pin "7") (pinfunction "A1_7") (pintype "output"))
    )
    (net (code "14") (name "/EN_C") (class "Default")
      (node (ref "R281") (pin "2") (pinfunction "2_2") (pintype "passive"))
      (node (ref "U26") (pin "6") (pinfunction "A2_6") (pintype "output"))
    )
    (net (code "15") (name "/EN_CH1") (class "Default")
      (node (ref "R226") (pin "2") (pinfunction "2_2") (pintype "passive"))
      (node (ref "S4") (pin "4") (pinfunction "4_4") (pintype "passive"))
      (node (ref "U26") (pin "10") (pinfunction "0_10") (pintype "input"))
    )
    (net (code "16") (name "/EN_CH2") (class "Default")
      (node (ref "R225") (pin "2") (pinfunction "2_2") (pintype "passive"))
      (node (ref "S4") (pin "3") (pinfunction "3_3") (pintype "passive"))
      (node (ref "U26") (pin "11") (pinfunction "1_11") (pintype "input"))
    )
    (net (code "17") (name "/EN_CH3") (class "Default")
      (node (ref "R224") (pin "2") (pinfunction "2_2") (pintype "passive"))
      (node (ref "S4") (pin "2") (pinfunction "2_2") (pintype "passive"))
      (node (ref "U26") (pin "12") (pinfunction "2_12") (pintype "input"))
    )
    (net (code "18") (name "/EN_CH4") (class "Default")
      (node (ref "R223") (pin "2") (pinfunction "2_2") (pintype "passive"))
      (node (ref "S4") (pin "1") (pinfunction "1_1") (pintype "passive"))
      (node (ref "U26") (pin "13") (pinfunction "3_13") (pintype "input"))
    )
    (net (code "19") (name "/EN_CH5") (class "Default")
      (node (ref "R227") (pin "2") (pinfunction "2_2") (pintype "passive"))
      (node (ref "S4") (pin "5") (pinfunction "5_5") (pintype "passive"))
      (node (ref "U26") (pin "1") (pinfunction "4_1") (pintype "input"))
    )
    (net (code "20") (name "/EN_CH6") (class "Default")
      (node (ref "R228") (pin "2") (pinfunction "2_2") (pintype "passive"))
      (node (ref "S4") (pin "6") (pinfunction "6_6") (pintype "passive"))
      (node (ref "U26") (pin "2") (pinfunction "5_2") (pintype "input"))
    )
    (net (code "21") (name "/EN_CH7") (class "Default")
      (node (ref "R229") (pin "2") (pinfunction "2_2") (pintype "passive"))
      (node (ref "S4") (pin "7") (pinfunction "7_7") (pintype "passive"))
      (node (ref "U26") (pin "3") (pinfunction "6_3") (pintype "input"))
    )
    (net (code "22") (name "/EN_CH8") (class "Default")
      (node (ref "R230") (pin "2") (pinfunction "2_2") (pintype "passive"))
      (node (ref "S4") (pin "8") (pinfunction "8_8") (pintype "passive"))
      (node (ref "U26") (pin "4") (pinfunction "7_4") (pintype "input"))
    )
    (net (code "25") (name "/FLASH.SPI_CLK") (class "Default")
      (node (ref "J7") (pin "6") (pinfunction "6_6") (pintype "passive"))
      (node (ref "U17") (pin "15") (pinfunction "FLASH_SPI_CLK_15") (pintype "input"))
    )
    (net (code "26") (name "/FLASH.SPI_CS") (class "Default")
      (node (ref "J7") (pin "7") (pinfunction "7_7") (pintype "passive"))
      (node (ref "U17") (pin "14") (pinfunction "FLASH_SPI_nCS_IN_14") (pintype "input"))
    )
    (net (code "27") (name "/FLASH.SPI_MISO") (class "Default")
      (node (ref "J7") (pin "8") (pinfunction "8_8") (pintype "passive"))
      (node (ref "U17") (pin "13") (pinfunction "FLASH_SPI_MISO_13") (pintype "input"))
    )
    (net (code "28") (name "/FLASH.SPI_MOSI") (class "Default")
      (node (ref "J7") (pin "9") (pinfunction "9_9") (pintype "passive"))
      (node (ref "U17") (pin "17") (pinfunction "FLASH_SPI_MOSI_17") (pintype "output"))
    )
    (net (code "29") (name "/GPIO.26") (class "Default")
      (node (ref "J5") (pin "42") (pinfunction "42_42") (pintype "passive"))
      (node (ref "R26") (pin "1") (pinfunction "1_1") (pintype "passive"))
      (node (ref "U24") (pin "6") (pinfunction "2Y_6") (pintype "output"))
    )
    (net (code "30") (name "/GPIO.27") (class "Default")
      (node (ref "J5") (pin "40") (pinfunction "40_40") (pintype "passive"))
      (node (ref "R26") (pin "2") (pinfunction "2_2") (pintype "passive"))
      (node (ref "U24") (pin "8") (pinfunction "3Y_8") (pintype "output"))
    )
    (net (code "31") (name "/GPIO.28") (class "Default")
      (node (ref "J5") (pin "45") (pinfunction "45_45") (pintype "passive"))
      (node (ref "R57") (pin "2") (pinfunction "2_2") (pintype "passive"))
      (node (ref "U24") (pin "3") (pinfunction "1Y_3") (pintype "output"))
    )
    (net (code "32") (name "/GPIO.34") (class "Default")
      (node (ref "J5") (pin "35") (pinfunction "35_35") (pintype "passive"))
      (node (ref "R48") (pin "2") (pinfunction "2_2") (pintype "passive"))
      (node (ref "U24") (pin "11") (pinfunction "4Y_11") (pintype "output"))
    )
    (net (code "33") (name "/GPIO.39") (class "Default")
      (node (ref "J5") (pin "33") (pinfunction "33_33") (pintype "passive"))
      (node (ref "R48") (pin "1") (pinfunction "1_1") (pintype "passive"))
      (node (ref "U28") (pin "3") (pinfunction "1Y_3") (pintype "output"))
    )
    (net (code "34") (name "/GPIO.44") (class "Default")
      (node (ref "J5") (pin "31") (pinfunction "31_31") (pintype "passive"))
      (node (ref "R50") (pin "2") (pinfunction "2_2") (pintype "passive"))
      (node (ref "U28") (pin "6") (pinfunction "2Y_6") (pintype "output"))
    )
    (net (code "35") (name "/GPIO.45") (class "Default")
      (node (ref "J5") (pin "29") (pinfunction "29_29") (pintype "passive"))
      (node (ref "R50") (pin "1") (pinfunction "1_1") (pintype "passive"))
      (node (ref "U28") (pin "8") (pinfunction "3Y_8") (pintype "output"))
    )
    (net (code "36") (name "/GPIO.46") (class "Default")
      (node (ref "J5") (pin "27") (pinfunction "27_27") (pintype "passive"))
      (node (ref "R58") (pin "2") (pinfunction "2_2") (pintype "passive"))
      (node (ref "U28") (pin "11") (pinfunction "4Y_11") (pintype "output"))
    )
    (net (code "38") (name "/MODE_A") (class "Default")
      (node (ref "R257") (pin "1") (pinfunction "1_1") (pintype "passive"))
      (node (ref "U27") (pin "9") (pinfunction "A0_9") (pintype "output"))
    )
    (net (code "39") (name "/MODE_B") (class "Default")
      (node (ref "R270") (pin "1") (pinfunction "1_1") (pintype "passive"))
      (node (ref "U27") (pin "7") (pinfunction "A1_7") (pintype "output"))
    )
    (net (code "40") (name "/MODE_C") (class "Default")
      (node (ref "R278") (pin "1") (pinfunction "1_1") (pintype "passive"))
      (node (ref "U27") (pin "6") (pinfunction "A2_6") (pintype "output"))
    )
    (net (code "41") (name "/MODE_CH1") (class "Default")
      (node (ref "R234") (pin "2") (pinfunction "2_2") (pintype "passive"))
      (node (ref "S5") (pin "4") (pinfunction "4_4") (pintype "passive"))
      (node (ref "U27") (pin "10") (pinfunction "0_10") (pintype "input"))
    )
    (net (code "42") (name "/MODE_CH2") (class "Default")
      (node (ref "R233") (pin "2") (pinfunction "2_2") (pintype "passive"))
      (node (ref "S5") (pin "3") (pinfunction "3_3") (pintype "passive"))
      (node (ref "U27") (pin "11") (pinfunction "1_11") (pintype "input"))
    )
    (net (code "43") (name "/MODE_CH3") (class "Default")
      (node (ref "R232") (pin "2") (pinfunction "2_2") (pintype "passive"))
      (node (ref "S5") (pin "2") (pinfunction "2_2") (pintype "passive"))
      (node (ref "U27") (pin "12") (pinfunction "2_12") (pintype "input"))
    )
    (net (code "44") (name "/MODE_CH4") (class "Default")
      (node (ref "R231") (pin "2") (pinfunction "2_2") (pintype "passive"))
      (node (ref "S5") (pin "1") (pinfunction "1_1") (pintype "passive"))
      (node (ref "U27") (pin "13") (pinfunction "3_13") (pintype "input"))
    )
    (net (code "45") (name "/MODE_CH5") (class "Default")
      (node (ref "R235") (pin "2") (pinfunction "2_2") (pintype "passive"))
      (node (ref "S5") (pin "5") (pinfunction "5_5") (pintype "passive"))
      (node (ref "U27") (pin "1") (pinfunction "4_1") (pintype "input"))
    )
    (net (code "46") (name "/MODE_CH6") (class "Default")
      (node (ref "R236") (pin "2") (pinfunction "2_2") (pintype "passive"))
      (node (ref "S5") (pin "6") (pinfunction "6_6") (pintype "passive"))
      (node (ref "U27") (pin "2") (pinfunction "5_2") (pintype "input"))
    )
    (net (code "47") (name "/MODE_CH7") (class "Default")
      (node (ref "R237") (pin "2") (pinfunction "2_2") (pintype "passive"))
      (node (ref "S5") (pin "7") (pinfunction "7_7") (pintype "passive"))
      (node (ref "U27") (pin "3") (pinfunction "6_3") (pintype "input"))
    )
    (net (code "48") (name "/MODE_CH8") (class "Default")
      (node (ref "R238") (pin "2") (pinfunction "2_2") (pintype "passive"))
      (node (ref "S5") (pin "8") (pinfunction "8_8") (pintype "passive"))
      (node (ref "U27") (pin "4") (pinfunction "7_4") (pintype "input"))
    )
    (net (code "49") (name "/RESET1") (class "Default")
      (node (ref "R284") (pin "1") (pinfunction "1_1") (pintype "passive"))
    )
    (net (code "50") (name "/RESET2") (class "Default")
      (node (ref "R239") (pin "1") (pinfunction "1_1") (pintype "passive"))
    )
    (net (code "52") (name "/SCIRXA") (class "Default")
      (node (ref "LED") (pin "3") (pinfunction "3_3") (pintype "passive"))
      (node (ref "R57") (pin "1") (pinfunction "1_1") (pintype "passive"))
    )
    (net (code "53") (name "/SCITXA") (class "Default")
      (node (ref "LED") (pin "2") (pinfunction "2_2") (pintype "passive"))
      (node (ref "R23") (pin "1") (pinfunction "1_1") (pintype "passive"))
    )
    (net (code "54") (name "/SCLB") (class "Default")
      (node (ref "R220") (pin "2") (pinfunction "2_2") (pintype "passive"))
      (node (ref "R241") (pin "1") (pinfunction "1_1") (pintype "passive"))
      (node (ref "U34") (pin "6") (pinfunction "SCL_6") (pintype "input"))
    )
    (net (code "55") (name "/SDAB") (class "Default")
      (node (ref "R242") (pin "1") (pinfunction "1_1") (pintype "passive"))
      (node (ref "R60") (pin "2") (pinfunction "2_2") (pintype "passive"))
      (node (ref "U34") (pin "5") (pinfunction "SDA_5") (pintype "bidirectional"))
    )
    (net (code "56") (name "/SPICLKA") (class "Default")
      (node (ref "R280") (pin "2") (pinfunction "2_2") (pintype "passive"))
    )
    (net (code "57") (name "/SPICLKC") (class "Default")
      (node (ref "R288") (pin "1") (pinfunction "1_1") (pintype "passive"))
    )
    (net (code "58") (name "/SPISIMOA") (class "Default")
      (node (ref "R277") (pin "1") (pinfunction "1_1") (pintype "passive"))
    )
    (net (code "59") (name "/SPISIMOC") (class "Default")
      (node (ref "R298") (pin "1") (pinfunction "1_1") (pintype "passive"))
    )
    (net (code "60") (name "/SPISOMIA") (class "Default")
      (node (ref "R279") (pin "1") (pinfunction "1_1") (pintype "passive"))
    )
    (net (code "61") (name "/SPISOMIC") (class "Default")
      (node (ref "R286") (pin "1") (pinfunction "1_1") (pintype "passive"))
    )
    (net (code "62") (name "/SPISTEA") (class "Default")
      (node (ref "R282") (pin "2") (pinfunction "2_2") (pintype "passive"))
    )
    (net (code "63") (name "/SPISTEC") (class "Default")
      (node (ref "R285") (pin "2") (pinfunction "2_2") (pintype "passive"))
    )
    (net (code "64") (name "/VinP") (class "Default")
      (node (ref "C169") (pin "1") (pinfunction "1_1") (pintype "passive"))
      (node (ref "C173") (pin "2") (pinfunction "2_2") (pintype "passive"))
      (node (ref "R247") (pin "1") (pinfunction "1_1") (pintype "passive"))
      (node (ref "R300") (pin "2") (pinfunction "2_2") (pintype "passive"))
    )
    (net (code "66") (name "/WIFI.JTAG_TCK") (class "Default")
      (node (ref "J6") (pin "4") (pinfunction "4_4") (pintype "passive"))
      (node (ref "R308") (pin "1") (pinfunction "1_1") (pintype "passive"))
      (node (ref "U17") (pin "21") (pinfunction "JTAG_TCK_21") (pintype "bidirectional"))
    )
    (net (code "67") (name "/WIFI.JTAG_TDI") (class "Default")
      (node (ref "J6") (pin "8") (pinfunction "8_8") (pintype "passive"))
      (node (ref "R309") (pin "1") (pinfunction "1_1") (pintype "passive"))
      (node (ref "U17") (pin "12") (pinfunction "JTAG_TDI_12") (pintype "bidirectional"))
    )
    (net (code "68") (name "/WIFI.JTAG_TDO") (class "Default")
      (node (ref "J6") (pin "6") (pinfunction "6_6") (pintype "passive"))
      (node (ref "U17") (pin "18") (pinfunction "JTAG_TDO_18") (pintype "bidirectional"))
    )
    (net (code "69") (name "/WIFI.JTAG_TMS") (class "Default")
      (node (ref "J6") (pin "2") (pinfunction "2_2") (pintype "passive"))
      (node (ref "R307") (pin "1") (pinfunction "1_1") (pintype "passive"))
      (node (ref "U17") (pin "22") (pinfunction "JTAG_TMS_22") (pintype "bidirectional"))
    )
    (net (code "70") (name "5V_D") (class "Default")
      (node (ref "J5") (pin "23") (pinfunction "23_23") (pintype "passive"))
      (node (ref "J5") (pin "37") (pinfunction "37_37") (pintype "passive"))
      (node (ref "J5") (pin "73") (pinfunction "73_73") (pintype "passive"))
      (node (ref "J5") (pin "9") (pinfunction "9_9") (pintype "passive"))
      (node (ref "J6") (pin "5") (pinfunction "5_5") (pintype "passive"))
      (node (ref "J7") (pin "5") (pinfunction "5_5") (pintype "passive"))
      (node (ref "P1") (pin "14") (pinfunction "14_14") (pintype "passive"))
      (node (ref "R165") (pin "1") (pinfunction "1_1") (pintype "passive"))
      (node (ref "U39") (pin "14") (pinfunction "5V_PWR_14") (pintype "power_in"))
    )
    (net (code "71") (name "12V_Out") (class "Default")
      (node (ref "C175") (pin "1") (pinfunction "1_1") (pintype "passive"))
      (node (ref "R299") (pin "1") (pinfunction "1_1") (pintype "passive"))
    )
    (net (code "72") (name "AGND") (class "Default")
      (node (ref "C169") (pin "2") (pinfunction "2_2") (pintype "passive"))
      (node (ref "C173") (pin "1") (pinfunction "1_1") (pintype "passive"))
      (node (ref "C175") (pin "2") (pinfunction "2_2") (pintype "passive"))
      (node (ref "C176") (pin "2") (pinfunction "2_2") (pintype "passive"))
      (node (ref "R260") (pin "2") (pinfunction "2_2") (pintype "passive"))
      (node (ref "R301") (pin "1") (pinfunction "1_1") (pintype "passive"))
      (node (ref "U14") (pin "2") (pinfunction "V-_2") (pintype "power_in"))
    )
    (net (code "73") (name "AVDD") (class "Default")
      (node (ref "C176") (pin "1") (pinfunction "1_1") (pintype "passive"))
      (node (ref "U14") (pin "5") (pinfunction "V+_5") (pintype "power_in"))
    )
    (net (code "74") (name "CANRXA") (class "Default")
      (node (ref "R289") (pin "1") (pinfunction "1_1") (pintype "passive"))
      (node (ref "U35") (pin "4") (pinfunction "R_4") (pintype "output"))
    )
    (net (code "75") (name "CANTXA") (class "Default")
      (node (ref "R27") (pin "1") (pinfunction "1_1") (pintype "passive"))
      (node (ref "U35") (pin "1") (pinfunction "D_1") (pintype "input"))
    )
    (net (code "76") (name "DGND") (class "Default")
      (node (ref "C124") (pin "2") (pinfunction "2_2") (pintype "passive"))
      (node (ref "C125") (pin "2") (pinfunction "2_2") (pintype "passive"))
      (node (ref "C126") (pin "2") (pinfunction "2_2") (pintype "passive"))
      (node (ref "C135") (pin "2") (pinfunction "2_2") (pintype "passive"))
      (node (ref "C150") (pin "2") (pinfunction "2_2") (pintype "passive"))
      (node (ref "C194") (pin "2") (pinfunction "2_2") (pintype "passive"))
      (node (ref "C195") (pin "2") (pinfunction "2_2") (pintype "passive"))
      (node (ref "C196") (pin "2") (pinfunction "2_2") (pintype "passive"))
      (node (ref "C197") (pin "2") (pinfunction "2_2") (pintype "passive"))
      (node (ref "C198") (pin "2") (pinfunction "2_2") (pintype "passive"))
      (node (ref "C32") (pin "1") (pinfunction "1_1") (pintype "passive"))
      (node (ref "C34") (pin "1") (pinfunction "1_1") (pintype "passive"))
      (node (ref "CAN") (pin "5") (pinfunction "5_5") (pintype "passive"))
      (node (ref "D33") (pin "1") (pinfunction "K_1") (pintype "passive"))
      (node (ref "I2C") (pin "3") (pinfunction "3_3") (pintype "passive"))
      (node (ref "J5") (pin "10") (pinfunction "10_10") (pintype "passive"))
      (node (ref "J5") (pin "102") (pinfunction "102_102") (pintype "passive"))
      (node (ref "J5") (pin "105") (pinfunction "105_105") (pintype "passive"))
      (node (ref "J5") (pin "108") (pinfunction "108_108") (pintype "passive"))
      (node (ref "J5") (pin "111") (pinfunction "111_111") (pintype "passive"))
      (node (ref "J5") (pin "114") (pinfunction "114_114") (pintype "passive"))
      (node (ref "J5") (pin "24") (pinfunction "24_24") (pintype "passive"))
      (node (ref "J5") (pin "38") (pinfunction "38_38") (pintype "passive"))
      (node (ref "J5") (pin "56") (pinfunction "56_56") (pintype "passive"))
      (node (ref "J5") (pin "74") (pinfunction "74_74") (pintype "passive"))
      (node (ref "J5") (pin "75") (pinfunction "75_75") (pintype "passive"))
      (node (ref "J5") (pin "83") (pinfunction "83_83") (pintype "passive"))
      (node (ref "J5") (pin "86") (pinfunction "86_86") (pintype "passive"))
      (node (ref "J5") (pin "92") (pinfunction "92_92") (pintype "passive"))
      (node (ref "J5") (pin "99") (pinfunction "99_99") (pintype "passive"))
      (node (ref "J5") (pin "G1") (pinfunction "121_G1") (pintype "bidirectional"))
      (node (ref "J5") (pin "G2") (pinfunction "122_G2") (pintype "bidirectional"))
      (node (ref "J6") (pin "3") (pinfunction "3_3") (pintype "passive"))
      (node (ref "J7") (pin "3") (pinfunction "3_3") (pintype "passive"))
      (node (ref "LED") (pin "4") (pinfunction "4_4") (pintype "passive"))
      (node (ref "P1") (pin "15") (pinfunction "15_15") (pintype "passive"))
      (node (ref "P2") (pin "1") (pinfunction "1_1") (pintype "passive"))
      (node (ref "P2") (pin "18") (pinfunction "18_18") (pintype "passive"))
      (node (ref "P2") (pin "7") (pinfunction "7_7") (pintype "passive"))
      (node (ref "P2") (pin "8") (pinfunction "8_8") (pintype "passive"))
      (node (ref "R244") (pin "1") (pinfunction "1_1") (pintype "passive"))
      (node (ref "R316") (pin "2") (pinfunction "2_2") (pintype "passive"))
      (node (ref "R317") (pin "1") (pinfunction "1_1") (pintype "passive"))
      (node (ref "R318") (pin "1") (pinfunction "1_1") (pintype "passive"))
      (node (ref "R320") (pin "1") (pinfunction "1_1") (pintype "passive"))
      (node (ref "R322") (pin "1") (pinfunction "1_1") (pintype "passive"))
      (node (ref "R324") (pin "1") (pinfunction "1_1") (pintype "passive"))
      (node (ref "R326") (pin "1") (pinfunction "1_1") (pintype "passive"))
      (node (ref "R329") (pin "1") (pinfunction "1_1") (pintype "passive"))
      (node (ref "R331") (pin "1") (pinfunction "1_1") (pintype "passive"))
      (node (ref "R333") (pin "1") (pinfunction "1_1") (pintype "passive"))
      (node (ref "R335") (pin "1") (pinfunction "1_1") (pintype "passive"))
      (node (ref "S4") (pin "10") (pinfunction "7A_10") (pintype "passive"))
      (node (ref "S4") (pin "11") (pinfunction "6A_11") (pintype "passive"))
      (node (ref "S4") (pin "12") (pinfunction "5A_12") (pintype "passive"))
      (node (ref "S4") (pin "13") (pinfunction "4A_13") (pintype "passive"))
      (node (ref "S4") (pin "14") (pinfunction "3A_14") (pintype "passive"))
      (node (ref "S4") (pin "15") (pinfunction "2A_15") (pintype "passive"))
      (node (ref "S4") (pin "16") (pinfunction "1A_16") (pintype "passive"))
      (node (ref "S4") (pin "9") (pinfunction "8A_9") (pintype "passive"))
      (node (ref "S5") (pin "10") (pinfunction "7A_10") (pintype "passive"))
      (node (ref "S5") (pin "11") (pinfunction "6A_11") (pintype "passive"))
      (node (ref "S5") (pin "12") (pinfunction "5A_12") (pintype "passive"))
      (node (ref "S5") (pin "13") (pinfunction "4A_13") (pintype "passive"))
      (node (ref "S5") (pin "14") (pinfunction "3A_14") (pintype "passive"))
      (node (ref "S5") (pin "15") (pinfunction "2A_15") (pintype "passive"))
      (node (ref "S5") (pin "16") (pinfunction "1A_16") (pintype "passive"))
      (node (ref "S5") (pin "9") (pinfunction "8A_9") (pintype "passive"))
      (node (ref "S6") (pin "2") (pinfunction "2_2") (pintype "passive"))
      (node (ref "TP41") (pin "1") (pintype "passive"))
      (node (ref "U17") (pin "1") (pinfunction "GND_1") (pintype "passive"))
      (node (ref "U17") (pin "16") (pinfunction "GND_16") (pintype "passive"))
      (node (ref "U17") (pin "2") (pinfunction "GND_2") (pintype "passive"))
      (node (ref "U17") (pin "27") (pinfunction "GND_27") (pintype "passive"))
      (node (ref "U17") (pin "28") (pinfunction "GND_28") (pintype "passive"))
      (node (ref "U17") (pin "30") (pinfunction "GND_30") (pintype "passive"))
      (node (ref "U17") (pin "32") (pinfunction "GND_32") (pintype "passive"))
      (node (ref "U17") (pin "38") (pinfunction "GND_38") (pintype "passive"))
      (node (ref "U17") (pin "43") (pinfunction "GND_43") (pintype "passive"))
      (node (ref "U17") (pin "PAD") (pinfunction "GND_PAD") (pintype "passive"))
      (node (ref "U18") (pin "5") (pinfunction "VCC_5") (pintype "power_in"))
      (node (ref "U24") (pin "7") (pinfunction "GND_7") (pintype "power_in"))
      (node (ref "U26") (pin "5") (pinfunction "EI_5") (pintype "input"))
      (node (ref "U26") (pin "8") (pinfunction "GND_8") (pintype "power_in"))
      (node (ref "U27") (pin "5") (pinfunction "EI_5") (pintype "input"))
      (node (ref "U27") (pin "8") (pinfunction "GND_8") (pintype "power_in"))
      (node (ref "U28") (pin "7") (pinfunction "GND_7") (pintype "power_in"))
      (node (ref "U34") (pin "2") (pinfunction "A1_2") (pintype "input"))
      (node (ref "U34") (pin "3") (pinfunction "A2_3") (pintype "input"))
      (node (ref "U34") (pin "4") (pinfunction "VSS_4") (pintype "power_in"))
      (node (ref "U35") (pin "2") (pinfunction "GND_2") (pintype "power_in"))
      (node (ref "U39") (pin "15") (pinfunction "GND_15") (pintype "power_in"))
      (node (ref "U39") (pin "16") (pinfunction "GND_16") (pintype "power_in"))
      (node (ref "U39") (pin "22") (pinfunction "GND_22") (pintype "power_in"))
      (node (ref "U39") (pin "23") (pinfunction "GND_23") (pintype "power_in"))
      (node (ref "U39") (pin "33") (pinfunction "GND_33") (pintype "power_in"))
    )
    (net (code "77") (name "DVDD") (class "Default")
      (node (ref "C124") (pin "1") (pinfunction "1_1") (pintype "passive"))
      (node (ref "C125") (pin "1") (pinfunction "1_1") (pintype "passive"))
      (node (ref "C135") (pin "1") (pinfunction "1_1") (pintype "passive"))
      (node (ref "C150") (pin "1") (pinfunction "1_1") (pintype "passive"))
      (node (ref "C194") (pin "1") (pinfunction "1_1") (pintype "passive"))
      (node (ref "C195") (pin "1") (pinfunction "1_1") (pintype "passive"))
      (node (ref "C196") (pin "1") (pinfunction "1_1") (pintype "passive"))
      (node (ref "C197") (pin "1") (pinfunction "1_1") (pintype "passive"))
      (node (ref "C198") (pin "1") (pinfunction "1_1") (pintype "passive"))
      (node (ref "J6") (pin "1") (pinfunction "1_1") (pintype "passive"))
      (node (ref "J7") (pin "1") (pinfunction "1_1") (pintype "passive"))
      (node (ref "R162") (pin "1") (pinfunction "1_1") (pintype "passive"))
      (node (ref "R164") (pin "1") (pinfunction "1_1") (pintype "passive"))
      (node (ref "R223") (pin "1") (pinfunction "1_1") (pintype "passive"))
      (node (ref "R224") (pin "1") (pinfunction "1_1") (pintype "passive"))
      (node (ref "R225") (pin "1") (pinfunction "1_1") (pintype "passive"))
      (node (ref "R226") (pin "1") (pinfunction "1_1") (pintype "passive"))
      (node (ref "R227") (pin "1") (pinfunction "1_1") (pintype "passive"))
      (node (ref "R228") (pin "1") (pinfunction "1_1") (pintype "passive"))
      (node (ref "R229") (pin "1") (pinfunction "1_1") (pintype "passive"))
      (node (ref "R230") (pin "1") (pinfunction "1_1") (pintype "passive"))
      (node (ref "R231") (pin "1") (pinfunction "1_1") (pintype "passive"))
      (node (ref "R232") (pin "1") (pinfunction "1_1") (pintype "passive"))
      (node (ref "R233") (pin "1") (pinfunction "1_1") (pintype "passive"))
      (node (ref "R234") (pin "1") (pinfunction "1_1") (pintype "passive"))
      (node (ref "R235") (pin "1") (pinfunction "1_1") (pintype "passive"))
      (node (ref "R236") (pin "1") (pinfunction "1_1") (pintype "passive"))
      (node (ref "R237") (pin "1") (pinfunction "1_1") (pintype "passive"))
      (node (ref "R238") (pin "1") (pinfunction "1_1") (pintype "passive"))
      (node (ref "R240") (pin "2") (pinfunction "2_2") (pintype "passive"))
      (node (ref "R241") (pin "2") (pinfunction "2_2") (pintype "passive"))
      (node (ref "R242") (pin "2") (pinfunction "2_2") (pintype "passive"))
      (node (ref "R258") (pin "2") (pinfunction "2_2") (pintype "passive"))
      (node (ref "R259") (pin "2") (pinfunction "2_2") (pintype "passive"))
      (node (ref "R306") (pin "2") (pinfunction "2_2") (pintype "passive"))
      (node (ref "R307") (pin "2") (pinfunction "2_2") (pintype "passive"))
      (node (ref "R308") (pin "2") (pinfunction "2_2") (pintype "passive"))
      (node (ref "R309") (pin "2") (pinfunction "2_2") (pintype "passive"))
      (node (ref "R312") (pin "2") (pinfunction "2_2") (pintype "passive"))
      (node (ref "R327") (pin "2") (pinfunction "2_2") (pintype "passive"))
      (node (ref "U17") (pin "37") (pinfunction "VBAT1_37") (pintype "power_in"))
      (node (ref "U17") (pin "40") (pinfunction "VBAT2_40") (pintype "power_in"))
      (node (ref "U18") (pin "2") (pinfunction "GND_2") (pintype "power_in"))
      (node (ref "U24") (pin "14") (pinfunction "VCC_14") (pintype "power_in"))
      (node (ref "U26") (pin "16") (pinfunction "VCC_16") (pintype "power_in"))
      (node (ref "U27") (pin "16") (pinfunction "VCC_16") (pintype "power_in"))
      (node (ref "U28") (pin "14") (pinfunction "VCC_14") (pintype "power_in"))
      (node (ref "U34") (pin "8") (pinfunction "VDD_8") (pintype "power_in"))
      (node (ref "U35") (pin "3") (pinfunction "VCC_3") (pintype "power_in"))
    )
    (net (code "78") (name "EPWM_A1") (class "Default")
      (node (ref "R261") (pin "1") (pinfunction "1_1") (pintype "passive"))
    )
    (net (code "79") (name "EPWM_A2") (class "Default")
      (node (ref "R265") (pin "1") (pinfunction "1_1") (pintype "passive"))
    )
    (net (code "80") (name "EPWM_A3") (class "Default")
      (node (ref "R262") (pin "1") (pinfunction "1_1") (pintype "passive"))
    )
    (net (code "81") (name "EPWM_A4") (class "Default")
      (node (ref "R266") (pin "1") (pinfunction "1_1") (pintype "passive"))
    )
    (net (code "82") (name "EPWM_A5") (class "Default")
      (node (ref "R269") (pin "1") (pinfunction "1_1") (pintype "passive"))
    )
    (net (code "83") (name "EPWM_A6") (class "Default")
      (node (ref "R273") (pin "1") (pinfunction "1_1") (pintype "passive"))
    )
    (net (code "84") (name "EPWM_A7") (class "Default")
      (node (ref "R293") (pin "2") (pinfunction "2_2") (pintype "passive"))
    )
    (net (code "85") (name "EPWM_A8") (class "Default")
      (node (ref "R295") (pin "2") (pinfunction "2_2") (pintype "passive"))
    )
    (net (code "86") (name "EPWM_B1") (class "Default")
      (node (ref "R263") (pin "1") (pinfunction "1_1") (pintype "passive"))
    )
    (net (code "87") (name "EPWM_B2") (class "Default")
      (node (ref "R267") (pin "1") (pinfunction "1_1") (pintype "passive"))
    )
    (net (code "88") (name "EPWM_B3") (class "Default")
      (node (ref "R264") (pin "1") (pinfunction "1_1") (pintype "passive"))
    )
    (net (code "89") (name "EPWM_B4") (class "Default")
      (node (ref "R268") (pin "1") (pinfunction "1_1") (pintype "passive"))
    )
    (net (code "90") (name "EPWM_B5") (class "Default")
      (node (ref "R271") (pin "1") (pinfunction "1_1") (pintype "passive"))
    )
    (net (code "91") (name "EPWM_B6") (class "Default")
      (node (ref "R275") (pin "1") (pinfunction "1_1") (pintype "passive"))
    )
    (net (code "92") (name "EPWM_B7") (class "Default")
      (node (ref "R294") (pin "2") (pinfunction "2_2") (pintype "passive"))
    )
    (net (code "93") (name "EPWM_B8") (class "Default")
      (node (ref "R274") (pin "1") (pinfunction "1_1") (pintype "passive"))
    )
    (net (code "94") (name "INnFAULT") (class "Default")
      (node (ref "R327") (pin "1") (pinfunction "1_1") (pintype "passive"))
      (node (ref "U18") (pin "1") (pinfunction "1A_1") (pintype "input"))
      (node (ref "U18") (pin "3") (pinfunction "2A_3") (pintype "input"))
    )
    (net (code "95") (name "IoutS1") (class "Default")
      (node (ref "R249") (pin "1") (pinfunction "1_1") (pintype "passive"))
    )
    (net (code "96") (name "IoutS2") (class "Default")
      (node (ref "R251") (pin "1") (pinfunction "1_1") (pintype "passive"))
    )
    (net (code "97") (name "IoutS3") (class "Default")
      (node (ref "R43") (pin "1") (pinfunction "1_1") (pintype "passive"))
    )
    (net (code "98") (name "IoutS4") (class "Default")
      (node (ref "R49") (pin "1") (pinfunction "1_1") (pintype "passive"))
    )
    (net (code "99") (name "IoutS5") (class "Default")
      (node (ref "R52") (pin "1") (pinfunction "1_1") (pintype "passive"))
    )
    (net (code "100") (name "IoutS6") (class "Default")
      (node (ref "R253") (pin "1") (pinfunction "1_1") (pintype "passive"))
    )
    (net (code "101") (name "IoutS7") (class "Default")
      (node (ref "R255") (pin "1") (pinfunction "1_1") (pintype "passive"))
    )
    (net (code "102") (name "IoutS8") (class "Default")
      (node (ref "R54") (pin "1") (pinfunction "1_1") (pintype "passive"))
    )
    (net (code "103") (name "Net-(C32-Pad2)") (class "Default")
      (node (ref "C32") (pin "2") (pinfunction "2_2") (pintype "passive"))
      (node (ref "C34") (pin "2") (pinfunction "2_2") (pintype "passive"))
      (node (ref "LED") (pin "1") (pinfunction "1_1") (pintype "passive"))
      (node (ref "R164") (pin "2") (pinfunction "2_2") (pintype "passive"))
      (node (ref "R165") (pin "2") (pinfunction "2_2") (pintype "passive"))
    )
    (net (code "104") (name "Net-(D13-K)") (class "Default")
      (node (ref "D13") (pin "1") (pinfunction "K_1") (pintype "passive"))
      (node (ref "J6") (pin "10") (pinfunction "10_10") (pintype "passive"))
      (node (ref "J7") (pin "10") (pinfunction "10_10") (pintype "passive"))
    )
    (net (code "105") (name "Net-(D16-K)") (class "Default")
      (node (ref "D16") (pin "1") (pinfunction "K_1") (pintype "passive"))
      (node (ref "R319") (pin "2") (pinfunction "2_2") (pintype "passive"))
    )
    (net (code "106") (name "Net-(D19-K)") (class "Default")
      (node (ref "D19") (pin "1") (pinfunction "K_1") (pintype "passive"))
      (node (ref "R321") (pin "2") (pinfunction "2_2") (pintype "passive"))
    )
    (net (code "107") (name "Net-(D20-K)") (class "Default")
      (node (ref "D20") (pin "1") (pinfunction "K_1") (pintype "passive"))
      (node (ref "R323") (pin "2") (pinfunction "2_2") (pintype "passive"))
    )
    (net (code "108") (name "Net-(D21-K)") (class "Default")
      (node (ref "D21") (pin "1") (pinfunction "K_1") (pintype "passive"))
      (node (ref "R325") (pin "2") (pinfunction "2_2") (pintype "passive"))
    )
    (net (code "109") (name "Net-(D22-K)") (class "Default")
      (node (ref "D22") (pin "1") (pinfunction "K_1") (pintype "passive"))
      (node (ref "R328") (pin "2") (pinfunction "2_2") (pintype "passive"))
    )
    (net (code "110") (name "Net-(D23-K)") (class "Default")
      (node (ref "D23") (pin "1") (pinfunction "K_1") (pintype "passive"))
      (node (ref "R330") (pin "2") (pinfunction "2_2") (pintype "passive"))
    )
    (net (code "111") (name "Net-(D24-K)") (class "Default")
      (node (ref "D24") (pin "1") (pinfunction "K_1") (pintype "passive"))
      (node (ref "R332") (pin "2") (pinfunction "2_2") (pintype "passive"))
    )
    (net (code "112") (name "Net-(D25-K)") (class "Default")
      (node (ref "D25") (pin "1") (pinfunction "K_1") (pintype "passive"))
      (node (ref "R334") (pin "2") (pinfunction "2_2") (pintype "passive"))
    )
    (net (code "113") (name "Net-(D33-A)") (class "Default")
      (node (ref "D33") (pin "2") (pinfunction "A_2") (pintype "passive"))
      (node (ref "R59") (pin "2") (pinfunction "2_2") (pintype "passive"))
    )
    (net (code "114") (name "Net-(J5-Pad11)") (class "Default")
      (node (ref "J5") (pin "11") (pinfunction "11_11") (pintype "passive"))
      (node (ref "R281") (pin "1") (pinfunction "1_1") (pintype "passive"))
    )
    (net (code "115") (name "Net-(J5-Pad12)") (class "Default")
      (node (ref "J5") (pin "12") (pinfunction "12_12") (pintype "passive"))
      (node (ref "R285") (pin "1") (pinfunction "1_1") (pintype "passive"))
    )
    (net (code "116") (name "Net-(J5-Pad13)") (class "Default")
      (node (ref "J5") (pin "13") (pinfunction "13_13") (pintype "passive"))
      (node (ref "R283") (pin "2") (pinfunction "2_2") (pintype "passive"))
    )
    (net (code "117") (name "Net-(J5-Pad14)") (class "Default")
      (node (ref "J5") (pin "14") (pinfunction "14_14") (pintype "passive"))
      (node (ref "R288") (pin "2") (pinfunction "2_2") (pintype "passive"))
    )
    (net (code "118") (name "Net-(J5-Pad15)") (class "Default")
      (node (ref "J5") (pin "15") (pinfunction "15_15") (pintype "passive"))
      (node (ref "R276") (pin "2") (pinfunction "2_2") (pintype "passive"))
    )
    (net (code "119") (name "Net-(J5-Pad16)") (class "Default")
      (node (ref "J5") (pin "16") (pinfunction "16_16") (pintype "passive"))
      (node (ref "R286") (pin "2") (pinfunction "2_2") (pintype "passive"))
    )
    (net (code "120") (name "Net-(J5-Pad17)") (class "Default")
      (node (ref "J5") (pin "17") (pinfunction "17_17") (pintype "passive"))
      (node (ref "R278") (pin "2") (pinfunction "2_2") (pintype "passive"))
    )
    (net (code "121") (name "Net-(J5-Pad18)") (class "Default")
      (node (ref "J5") (pin "18") (pinfunction "18_18") (pintype "passive"))
      (node (ref "R298") (pin "2") (pinfunction "2_2") (pintype "passive"))
    )
    (net (code "122") (name "Net-(J5-Pad19)") (class "Default")
      (node (ref "J5") (pin "19") (pinfunction "19_19") (pintype "passive"))
      (node (ref "R270") (pin "2") (pinfunction "2_2") (pintype "passive"))
    )
    (net (code "123") (name "Net-(J5-Pad20)") (class "Default")
      (node (ref "J5") (pin "20") (pinfunction "20_20") (pintype "passive"))
      (node (ref "R297") (pin "2") (pinfunction "2_2") (pintype "passive"))
    )
    (net (code "124") (name "Net-(J5-Pad21)") (class "Default")
      (node (ref "J5") (pin "21") (pinfunction "21_21") (pintype "passive"))
      (node (ref "R257") (pin "2") (pinfunction "2_2") (pintype "passive"))
    )
    (net (code "125") (name "Net-(J5-Pad22)") (class "Default")
      (node (ref "J5") (pin "22") (pinfunction "22_22") (pintype "passive"))
      (node (ref "R239") (pin "2") (pinfunction "2_2") (pintype "passive"))
    )
    (net (code "126") (name "Net-(J5-Pad25)") (class "Default")
      (node (ref "J5") (pin "25") (pinfunction "25_25") (pintype "passive"))
      (node (ref "R59") (pin "1") (pinfunction "1_1") (pintype "passive"))
    )
    (net (code "127") (name "Net-(J5-Pad26)") (class "Default")
      (node (ref "J5") (pin "26") (pinfunction "26_26") (pintype "passive"))
      (node (ref "R222") (pin "1") (pinfunction "1_1") (pintype "passive"))
    )
    (net (code "128") (name "Net-(J5-Pad28)") (class "Default")
      (node (ref "J5") (pin "28") (pinfunction "28_28") (pintype "passive"))
      (node (ref "R296") (pin "1") (pinfunction "1_1") (pintype "passive"))
    )
    (net (code "129") (name "Net-(J5-Pad30)") (class "Default")
      (node (ref "J5") (pin "30") (pinfunction "30_30") (pintype "passive"))
      (node (ref "R220") (pin "1") (pinfunction "1_1") (pintype "passive"))
    )
    (net (code "130") (name "Net-(J5-Pad32)") (class "Default")
      (node (ref "J5") (pin "32") (pinfunction "32_32") (pintype "passive"))
      (node (ref "R60") (pin "1") (pinfunction "1_1") (pintype "passive"))
    )
    (net (code "131") (name "Net-(J5-Pad34)") (class "Default")
      (node (ref "J5") (pin "34") (pinfunction "34_34") (pintype "passive"))
      (node (ref "R187") (pin "1") (pinfunction "1_1") (pintype "passive"))
    )
    (net (code "132") (name "Net-(J5-Pad36)") (class "Default")
      (node (ref "J5") (pin "36") (pinfunction "36_36") (pintype "passive"))
      (node (ref "R173") (pin "1") (pinfunction "1_1") (pintype "passive"))
    )
    (net (code "133") (name "Net-(J5-Pad39)") (class "Default")
      (node (ref "J5") (pin "39") (pinfunction "39_39") (pintype "passive"))
      (node (ref "R27") (pin "2") (pinfunction "2_2") (pintype "passive"))
    )
    (net (code "134") (name "Net-(J5-Pad41)") (class "Default")
      (node (ref "J5") (pin "41") (pinfunction "41_41") (pintype "passive"))
      (node (ref "R289") (pin "2") (pinfunction "2_2") (pintype "passive"))
    )
    (net (code "135") (name "Net-(J5-Pad43)") (class "Default")
      (node (ref "J5") (pin "43") (pinfunction "43_43") (pintype "passive"))
      (node (ref "R23") (pin "2") (pinfunction "2_2") (pintype "passive"))
    )
    (net (code "136") (name "Net-(J5-Pad44)") (class "Default")
      (node (ref "J5") (pin "44") (pinfunction "44_44") (pintype "passive"))
      (node (ref "R272") (pin "1") (pinfunction "1_1") (pintype "passive"))
    )
    (net (code "137") (name "Net-(J5-Pad46)") (class "Default")
      (node (ref "J5") (pin "46") (pinfunction "46_46") (pintype "passive"))
      (node (ref "R284") (pin "2") (pinfunction "2_2") (pintype "passive"))
    )
    (net (code "138") (name "Net-(J5-Pad48)") (class "Default")
      (node (ref "J5") (pin "48") (pinfunction "48_48") (pintype "passive"))
      (node (ref "R282") (pin "1") (pinfunction "1_1") (pintype "passive"))
    )
    (net (code "139") (name "Net-(J5-Pad49)") (class "Default")
      (node (ref "J5") (pin "49") (pinfunction "49_49") (pintype "passive"))
      (node (ref "R56") (pin "1") (pinfunction "1_1") (pintype "passive"))
    )
    (net (code "140") (name "Net-(J5-Pad50)") (class "Default")
      (node (ref "J5") (pin "50") (pinfunction "50_50") (pintype "passive"))
      (node (ref "R280") (pin "1") (pinfunction "1_1") (pintype "passive"))
    )
    (net (code "141") (name "Net-(J5-Pad52)") (class "Default")
      (node (ref "J5") (pin "52") (pinfunction "52_52") (pintype "passive"))
      (node (ref "R279") (pin "2") (pinfunction "2_2") (pintype "passive"))
    )
    (net (code "142") (name "Net-(J5-Pad53)") (class "Default")
      (node (ref "J5") (pin "53") (pinfunction "53_53") (pintype "passive"))
      (node (ref "R292") (pin "1") (pinfunction "1_1") (pintype "passive"))
    )
    (net (code "143") (name "Net-(J5-Pad54)") (class "Default")
      (node (ref "J5") (pin "54") (pinfunction "54_54") (pintype "passive"))
      (node (ref "R277") (pin "2") (pinfunction "2_2") (pintype "passive"))
    )
    (net (code "144") (name "Net-(J5-Pad57)") (class "Default")
      (node (ref "J5") (pin "57") (pinfunction "57_57") (pintype "passive"))
      (node (ref "R274") (pin "2") (pinfunction "2_2") (pintype "passive"))
    )
    (net (code "145") (name "Net-(J5-Pad58)") (class "Default")
      (node (ref "J5") (pin "58") (pinfunction "58_58") (pintype "passive"))
      (node (ref "R275") (pin "2") (pinfunction "2_2") (pintype "passive"))
    )
    (net (code "146") (name "Net-(J5-Pad59)") (class "Default")
      (node (ref "J5") (pin "59") (pinfunction "59_59") (pintype "passive"))
      (node (ref "R295") (pin "1") (pinfunction "1_1") (pintype "passive"))
    )
    (net (code "147") (name "Net-(J5-Pad60)") (class "Default")
      (node (ref "J5") (pin "60") (pinfunction "60_60") (pintype "passive"))
      (node (ref "R273") (pin "2") (pinfunction "2_2") (pintype "passive"))
    )
    (net (code "148") (name "Net-(J5-Pad61)") (class "Default")
      (node (ref "J5") (pin "61") (pinfunction "61_61") (pintype "passive"))
      (node (ref "R294") (pin "1") (pinfunction "1_1") (pintype "passive"))
    )
    (net (code "149") (name "Net-(J5-Pad62)") (class "Default")
      (node (ref "J5") (pin "62") (pinfunction "62_62") (pintype "passive"))
      (node (ref "R271") (pin "2") (pinfunction "2_2") (pintype "passive"))
    )
    (net (code "150") (name "Net-(J5-Pad63)") (class "Default")
      (node (ref "J5") (pin "63") (pinfunction "63_63") (pintype "passive"))
      (node (ref "R293") (pin "1") (pinfunction "1_1") (pintype "passive"))
    )
    (net (code "151") (name "Net-(J5-Pad64)") (class "Default")
      (node (ref "J5") (pin "64") (pinfunction "64_64") (pintype "passive"))
      (node (ref "R269") (pin "2") (pinfunction "2_2") (pintype "passive"))
    )
    (net (code "152") (name "Net-(J5-Pad65)") (class "Default")
      (node (ref "J5") (pin "65") (pinfunction "65_65") (pintype "passive"))
      (node (ref "R268") (pin "2") (pinfunction "2_2") (pintype "passive"))
    )
    (net (code "153") (name "Net-(J5-Pad66)") (class "Default")
      (node (ref "J5") (pin "66") (pinfunction "66_66") (pintype "passive"))
      (node (ref "R267") (pin "2") (pinfunction "2_2") (pintype "passive"))
    )
    (net (code "154") (name "Net-(J5-Pad67)") (class "Default")
      (node (ref "J5") (pin "67") (pinfunction "67_67") (pintype "passive"))
      (node (ref "R266") (pin "2") (pinfunction "2_2") (pintype "passive"))
    )
    (net (code "155") (name "Net-(J5-Pad68)") (class "Default")
      (node (ref "J5") (pin "68") (pinfunction "68_68") (pintype "passive"))
      (node (ref "R265") (pin "2") (pinfunction "2_2") (pintype "passive"))
    )
    (net (code "156") (name "Net-(J5-Pad69)") (class "Default")
      (node (ref "J5") (pin "69") (pinfunction "69_69") (pintype "passive"))
      (node (ref "R264") (pin "2") (pinfunction "2_2") (pintype "passive"))
    )
    (net (code "157") (name "Net-(J5-Pad70)") (class "Default")
      (node (ref "J5") (pin "70") (pinfunction "70_70") (pintype "passive"))
      (node (ref "R263") (pin "2") (pinfunction "2_2") (pintype "passive"))
    )
    (net (code "158") (name "Net-(J5-Pad71)") (class "Default")
      (node (ref "J5") (pin "71") (pinfunction "71_71") (pintype "passive"))
      (node (ref "R262") (pin "2") (pinfunction "2_2") (pintype "passive"))
    )
    (net (code "159") (name "Net-(J5-Pad72)") (class "Default")
      (node (ref "J5") (pin "72") (pinfunction "72_72") (pintype "passive"))
      (node (ref "R261") (pin "2") (pinfunction "2_2") (pintype "passive"))
    )
    (net (code "160") (name "Net-(J5-Pad81)") (class "Default")
      (node (ref "J5") (pin "81") (pinfunction "81_81") (pintype "passive"))
      (node (ref "R22") (pin "2") (pinfunction "2_2") (pintype "passive"))
    )
    (net (code "161") (name "Net-(J5-Pad82)") (class "Default")
      (node (ref "J5") (pin "82") (pinfunction "82_82") (pintype "passive"))
      (node (ref "R22") (pin "1") (pinfunction "1_1") (pintype "passive"))
      (node (ref "R55") (pin "2") (pinfunction "2_2") (pintype "passive"))
    )
    (net (code "162") (name "Net-(J5-Pad84)") (class "Default")
      (node (ref "J5") (pin "84") (pinfunction "84_84") (pintype "passive"))
      (node (ref "R54") (pin "2") (pinfunction "2_2") (pintype "passive"))
    )
    (net (code "163") (name "Net-(J5-Pad85)") (class "Default")
      (node (ref "J5") (pin "85") (pinfunction "85_85") (pintype "passive"))
      (node (ref "R256") (pin "2") (pinfunction "2_2") (pintype "passive"))
    )
    (net (code "164") (name "Net-(J5-Pad87)") (class "Default")
      (node (ref "J5") (pin "87") (pinfunction "87_87") (pintype "passive"))
      (node (ref "R255") (pin "2") (pinfunction "2_2") (pintype "passive"))
    )
    (net (code "165") (name "Net-(J5-Pad88)") (class "Default")
      (node (ref "J5") (pin "88") (pinfunction "88_88") (pintype "passive"))
      (node (ref "R254") (pin "2") (pinfunction "2_2") (pintype "passive"))
    )
    (net (code "166") (name "Net-(J5-Pad90)") (class "Default")
      (node (ref "J5") (pin "90") (pinfunction "90_90") (pintype "passive"))
      (node (ref "R253") (pin "2") (pinfunction "2_2") (pintype "passive"))
    )
    (net (code "167") (name "Net-(J5-Pad91)") (class "Default")
      (node (ref "J5") (pin "91") (pinfunction "91_91") (pintype "passive"))
      (node (ref "R53") (pin "2") (pinfunction "2_2") (pintype "passive"))
    )
    (net (code "168") (name "Net-(J5-Pad93)") (class "Default")
      (node (ref "J5") (pin "93") (pinfunction "93_93") (pintype "passive"))
      (node (ref "R52") (pin "2") (pinfunction "2_2") (pintype "passive"))
    )
    (net (code "169") (name "Net-(J5-Pad94)") (class "Default")
      (node (ref "J5") (pin "94") (pinfunction "94_94") (pintype "passive"))
      (node (ref "R51") (pin "2") (pinfunction "2_2") (pintype "passive"))
    )
    (net (code "170") (name "Net-(J5-Pad96)") (class "Default")
      (node (ref "J5") (pin "96") (pinfunction "96_96") (pintype "passive"))
      (node (ref "R49") (pin "2") (pinfunction "2_2") (pintype "passive"))
    )
    (net (code "171") (name "Net-(J5-Pad98)") (class "Default")
      (node (ref "J5") (pin "98") (pinfunction "98_98") (pintype "passive"))
      (node (ref "R47") (pin "2") (pinfunction "2_2") (pintype "passive"))
    )
    (net (code "172") (name "Net-(J5-Pad100)") (class "Default")
      (node (ref "J5") (pin "100") (pinfunction "100_100") (pintype "passive"))
      (node (ref "R43") (pin "2") (pinfunction "2_2") (pintype "passive"))
    )
    (net (code "173") (name "Net-(J5-Pad101)") (class "Default")
      (node (ref "J5") (pin "101") (pinfunction "101_101") (pintype "passive"))
      (node (ref "R252") (pin "2") (pinfunction "2_2") (pintype "passive"))
    )
    (net (code "174") (name "Net-(J5-Pad103)") (class "Default")
      (node (ref "J5") (pin "103") (pinfunction "103_103") (pintype "passive"))
      (node (ref "R251") (pin "2") (pinfunction "2_2") (pintype "passive"))
    )
    (net (code "175") (name "Net-(J5-Pad104)") (class "Default")
      (node (ref "J5") (pin "104") (pinfunction "104_104") (pintype "passive"))
      (node (ref "R250") (pin "2") (pinfunction "2_2") (pintype "passive"))
    )
    (net (code "176") (name "Net-(J5-Pad106)") (class "Default")
      (node (ref "J5") (pin "106") (pinfunction "106_106") (pintype "passive"))
      (node (ref "R249") (pin "2") (pinfunction "2_2") (pintype "passive"))
    )
    (net (code "177") (name "Net-(J5-Pad109)") (class "Default")
      (node (ref "J5") (pin "109") (pinfunction "109_109") (pintype "passive"))
      (node (ref "R247") (pin "2") (pinfunction "2_2") (pintype "passive"))
    )
    (net (code "178") (name "Net-(J5-Pad112)") (class "Default")
      (node (ref "J5") (pin "112") (pinfunction "112_112") (pintype "passive"))
      (node (ref "R245") (pin "2") (pinfunction "2_2") (pintype "passive"))
    )
    (net (code "179") (name "Net-(P1-Pad1)") (class "Default")
      (node (ref "P1") (pin "1") (pinfunction "1_1") (pintype "passive"))
      (node (ref "U39") (pin "1") (pinfunction "3V3_1") (pintype "power_in"))
    )
    (net (code "180") (name "Net-(P2-Pad4)") (class "Default")
      (node (ref "P2") (pin "4") (pinfunction "4_4") (pintype "passive"))
      (node (ref "U39") (pin "19") (pinfunction "3V3_19") (pintype "power_in"))
    )
    (net (code "181") (name "Net-(P2-Pad13)") (class "Default")
      (node (ref "P2") (pin "13") (pinfunction "13_13") (pintype "passive"))
      (node (ref "U39") (pin "28") (pinfunction "3V3_28") (pintype "power_in"))
    )
    (net (code "182") (name "Net-(R312-Pad1)") (class "Default")
      (node (ref "R312") (pin "1") (pinfunction "1_1") (pintype "passive"))
      (node (ref "R313") (pin "1") (pinfunction "1_1") (pintype "passive"))
      (node (ref "R314") (pin "1") (pinfunction "1_1") (pintype "passive"))
      (node (ref "R315") (pin "1") (pinfunction "1_1") (pintype "passive"))
    )
    (net (code "183") (name "Net-(U14-IN+)") (class "Default")
      (node (ref "R260") (pin "1") (pinfunction "1_1") (pintype "passive"))
      (node (ref "R299") (pin "2") (pinfunction "2_2") (pintype "passive"))
      (node (ref "U14") (pin "3") (pinfunction "IN+_3") (pintype "input"))
    )
    (net (code "184") (name "Net-(U14-IN-)") (class "Default")
      (node (ref "C186") (pin "1") (pinfunction "1_1") (pintype "passive"))
      (node (ref "R301") (pin "2") (pinfunction "2_2") (pintype "passive"))
      (node (ref "R303") (pin "2") (pinfunction "2_2") (pintype "passive"))
      (node (ref "U14") (pin "4") (pinfunction "IN-_4") (pintype "input"))
    )
    (net (code "185") (name "Net-(U14-OUT)") (class "Default")
      (node (ref "C186") (pin "2") (pinfunction "2_2") (pintype "passive"))
      (node (ref "R300") (pin "1") (pinfunction "1_1") (pintype "passive"))
      (node (ref "R303") (pin "1") (pinfunction "1_1") (pintype "passive"))
      (node (ref "U14") (pin "1") (pinfunction "OUT_1") (pintype "output"))
    )
    (net (code "186") (name "Net-(U17-GPIO11)") (class "Default")
      (node (ref "R310") (pin "1") (pinfunction "1_1") (pintype "passive"))
      (node (ref "U17") (pin "4") (pinfunction "GPIO11_4") (pintype "bidirectional"))
    )
    (net (code "187") (name "Net-(U17-GPIO14)") (class "Default")
      (node (ref "R311") (pin "1") (pinfunction "1_1") (pintype "passive"))
      (node (ref "U17") (pin "5") (pinfunction "GPIO14_5") (pintype "bidirectional"))
    )
    (net (code "188") (name "Net-(U17-SOP0)") (class "Default")
      (node (ref "R313") (pin "2") (pinfunction "2_2") (pintype "passive"))
      (node (ref "R318") (pin "2") (pinfunction "2_2") (pintype "passive"))
      (node (ref "U17") (pin "34") (pinfunction "SOP0_34") (pintype "passive"))
    )
    (net (code "189") (name "Net-(U17-SOP1)") (class "Default")
      (node (ref "R314") (pin "2") (pinfunction "2_2") (pintype "passive"))
      (node (ref "R317") (pin "2") (pinfunction "2_2") (pintype "passive"))
      (node (ref "U17") (pin "24") (pinfunction "SOP1_24") (pintype "passive"))
    )
    (net (code "190") (name "Net-(U17-SOP2)") (class "Default")
      (node (ref "R315") (pin "2") (pinfunction "2_2") (pintype "passive"))
      (node (ref "R316") (pin "1") (pinfunction "1_1") (pintype "passive"))
      (node (ref "U17") (pin "23") (pinfunction "SOP2_23") (pintype "passive"))
    )
    (net (code "191") (name "Net-(U18A-1Y)") (class "Default")
      (node (ref "U18") (pin "6") (pinfunction "1Y_6") (pintype "output"))
      (node (ref "U24") (pin "1") (pinfunction "1A_1") (pintype "input"))
      (node (ref "U24") (pin "12") (pinfunction "4A_12") (pintype "input"))
      (node (ref "U24") (pin "4") (pinfunction "2A_4") (pintype "input"))
      (node (ref "U24") (pin "9") (pinfunction "3A_9") (pintype "input"))
    )
    (net (code "192") (name "Net-(U18B-2Y)") (class "Default")
      (node (ref "U18") (pin "4") (pinfunction "2Y_4") (pintype "output"))
      (node (ref "U28") (pin "1") (pinfunction "1A_1") (pintype "input"))
      (node (ref "U28") (pin "12") (pinfunction "4A_12") (pintype "input"))
      (node (ref "U28") (pin "4") (pinfunction "2A_4") (pintype "input"))
      (node (ref "U28") (pin "9") (pinfunction "3A_9") (pintype "input"))
    )
    (net (code "193") (name "Net-(U24A-1B)") (class "Default")
      (node (ref "R319") (pin "1") (pinfunction "1_1") (pintype "passive"))
      (node (ref "R320") (pin "2") (pinfunction "2_2") (pintype "passive"))
      (node (ref "U24") (pin "2") (pinfunction "1B_2") (pintype "input"))
    )
    (net (code "194") (name "Net-(U24B-2B)") (class "Default")
      (node (ref "R321") (pin "1") (pinfunction "1_1") (pintype "passive"))
      (node (ref "R322") (pin "2") (pinfunction "2_2") (pintype "passive"))
      (node (ref "U24") (pin "5") (pinfunction "2B_5") (pintype "input"))
    )
    (net (code "195") (name "Net-(U24C-3B)") (class "Default")
      (node (ref "R323") (pin "1") (pinfunction "1_1") (pintype "passive"))
      (node (ref "R324") (pin "2") (pinfunction "2_2") (pintype "passive"))
      (node (ref "U24") (pin "10") (pinfunction "3B_10") (pintype "input"))
    )
    (net (code "196") (name "Net-(U24D-4B)") (class "Default")
      (node (ref "R325") (pin "1") (pinfunction "1_1") (pintype "passive"))
      (node (ref "R326") (pin "2") (pinfunction "2_2") (pintype "passive"))
      (node (ref "U24") (pin "13") (pinfunction "4B_13") (pintype "input"))
    )
    (net (code "197") (name "Net-(U28A-1B)") (class "Default")
      (node (ref "R328") (pin "1") (pinfunction "1_1") (pintype "passive"))
      (node (ref "R329") (pin "2") (pinfunction "2_2") (pintype "passive"))
      (node (ref "U28") (pin "2") (pinfunction "1B_2") (pintype "input"))
    )
    (net (code "198") (name "Net-(U28B-2B)") (class "Default")
      (node (ref "R330") (pin "1") (pinfunction "1_1") (pintype "passive"))
      (node (ref "R331") (pin "2") (pinfunction "2_2") (pintype "passive"))
      (node (ref "U28") (pin "5") (pinfunction "2B_5") (pintype "input"))
    )
    (net (code "199") (name "Net-(U28C-3B)") (class "Default")
      (node (ref "R332") (pin "1") (pinfunction "1_1") (pintype "passive"))
      (node (ref "R333") (pin "2") (pinfunction "2_2") (pintype "passive"))
      (node (ref "U28") (pin "10") (pinfunction "3B_10") (pintype "input"))
    )
    (net (code "200") (name "Net-(U28D-4B)") (class "Default")
      (node (ref "R334") (pin "1") (pinfunction "1_1") (pintype "passive"))
      (node (ref "R335") (pin "2") (pinfunction "2_2") (pintype "passive"))
      (node (ref "U28") (pin "13") (pinfunction "4B_13") (pintype "input"))
    )
    (net (code "201") (name "Net-(U34-WP)") (class "Default")
      (node (ref "R162") (pin "2") (pinfunction "2_2") (pintype "passive"))
      (node (ref "U34") (pin "7") (pinfunction "WP_7") (pintype "input"))
    )
    (net (code "202") (name "Net-(U35-CANH)") (class "Default")
      (node (ref "CAN") (pin "1") (pinfunction "1_1") (pintype "passive"))
      (node (ref "CAN") (pin "2") (pinfunction "2_2") (pintype "passive"))
      (node (ref "R243") (pin "2") (pinfunction "2_2") (pintype "passive"))
      (node (ref "U35") (pin "7") (pinfunction "CANH_7") (pintype "bidirectional"))
    )
    (net (code "203") (name "Net-(U35-CANL)") (class "Default")
      (node (ref "CAN") (pin "3") (pinfunction "3_3") (pintype "passive"))
      (node (ref "CAN") (pin "4") (pinfunction "4_4") (pintype "passive"))
      (node (ref "R243") (pin "1") (pinfunction "1_1") (pintype "passive"))
      (node (ref "U35") (pin "6") (pinfunction "CANL_6") (pintype "bidirectional"))
    )
    (net (code "204") (name "Net-(U35-EN)") (class "Default")
      (node (ref "R240") (pin "1") (pinfunction "1_1") (pintype "passive"))
      (node (ref "U35") (pin "5") (pinfunction "EN_5") (pintype "input"))
    )
    (net (code "205") (name "Net-(U35-RS)") (class "Default")
      (node (ref "R244") (pin "2") (pinfunction "2_2") (pintype "passive"))
      (node (ref "U35") (pin "8") (pinfunction "RS_8") (pintype "input"))
    )
    (net (code "206") (name "Net-(U39-A0{slash}36{slash}VP)") (class "Default")
      (node (ref "P1") (pin "3") (pinfunction "3_3") (pintype "passive"))
      (node (ref "U39") (pin "3") (pinfunction "A0/36/VP_3") (pintype "bidirectional"))
    )
    (net (code "207") (name "Net-(U39-A3{slash}39{slash}VN)") (class "Default")
      (node (ref "P1") (pin "4") (pinfunction "4_4") (pintype "passive"))
      (node (ref "U39") (pin "4") (pinfunction "A3/39/VN_4") (pintype "bidirectional"))
    )
    (net (code "208") (name "Net-(U39-A4{slash}32)") (class "Default")
      (node (ref "P1") (pin "5") (pinfunction "5_5") (pintype "passive"))
      (node (ref "U39") (pin "5") (pinfunction "A4/32_5") (pintype "bidirectional"))
    )
    (net (code "209") (name "Net-(U39-A5{slash}33)") (class "Default")
      (node (ref "P1") (pin "6") (pinfunction "6_6") (pintype "passive"))
      (node (ref "U39") (pin "6") (pinfunction "A5/33_6") (pintype "bidirectional"))
    )
    (net (code "210") (name "Net-(U39-A6{slash}34)") (class "Default")
      (node (ref "P1") (pin "7") (pinfunction "7_7") (pintype "passive"))
      (node (ref "U39") (pin "7") (pinfunction "A6/34_7") (pintype "bidirectional"))
    )
    (net (code "211") (name "Net-(U39-A7{slash}35)") (class "Default")
      (node (ref "P1") (pin "8") (pinfunction "8_8") (pintype "passive"))
      (node (ref "U39") (pin "8") (pinfunction "A7/35_8") (pintype "bidirectional"))
    )
    (net (code "212") (name "Net-(U39-A14{slash}12)") (class "Default")
      (node (ref "P1") (pin "13") (pinfunction "13_13") (pintype "passive"))
      (node (ref "U39") (pin "13") (pinfunction "A14/12_13") (pintype "bidirectional"))
    )
    (net (code "213") (name "Net-(U39-A16{slash}14)") (class "Default")
      (node (ref "P1") (pin "12") (pinfunction "12_12") (pintype "passive"))
      (node (ref "U39") (pin "12") (pinfunction "A16/14_12") (pintype "bidirectional"))
    )
    (net (code "214") (name "Net-(U39-A17{slash}27)") (class "Default")
      (node (ref "P1") (pin "11") (pinfunction "11_11") (pintype "passive"))
      (node (ref "U39") (pin "11") (pinfunction "A17/27_11") (pintype "bidirectional"))
    )
    (net (code "215") (name "Net-(U39-A18{slash}DAC1{slash}25)") (class "Default")
      (node (ref "P1") (pin "9") (pinfunction "9_9") (pintype "passive"))
      (node (ref "U39") (pin "9") (pinfunction "A18/DAC1/25_9") (pintype "bidirectional"))
    )
    (net (code "216") (name "Net-(U39-A19{slash}DAC2{slash}26)") (class "Default")
      (node (ref "P1") (pin "10") (pinfunction "10_10") (pintype "passive"))
      (node (ref "U39") (pin "10") (pinfunction "A19/DAC2/26_10") (pintype "bidirectional"))
    )
    (net (code "217") (name "Net-(U39-ENABLE)") (class "Default")
      (node (ref "P1") (pin "2") (pinfunction "2_2") (pintype "passive"))
      (node (ref "U39") (pin "2") (pinfunction "ENABLE_2") (pintype "input"))
    )
    (net (code "218") (name "Net-(U39-GPIO_0)") (class "Default")
      (node (ref "P2") (pin "17") (pinfunction "17_17") (pintype "passive"))
      (node (ref "U39") (pin "32") (pinfunction "GPIO_0_32") (pintype "power_in"))
    )
    (net (code "219") (name "Net-(U39-GPIO_2)") (class "Default")
      (node (ref "P2") (pin "19") (pinfunction "19_19") (pintype "passive"))
      (node (ref "U39") (pin "34") (pinfunction "GPIO_2_34") (pintype "power_in"))
    )
    (net (code "220") (name "Net-(U39-GPIO_4)") (class "Default")
      (node (ref "P2") (pin "16") (pinfunction "16_16") (pintype "passive"))
      (node (ref "U39") (pin "31") (pinfunction "GPIO_4_31") (pintype "power_in"))
    )
    (net (code "221") (name "Net-(U39-GPIO_15)") (class "Default")
      (node (ref "P2") (pin "20") (pinfunction "20_20") (pintype "passive"))
      (node (ref "U39") (pin "35") (pinfunction "GPIO_15_35") (pintype "power_in"))
    )
    (net (code "222") (name "Net-(U39-GPIO_16)") (class "Default")
      (node (ref "P2") (pin "15") (pinfunction "15_15") (pintype "passive"))
      (node (ref "U39") (pin "30") (pinfunction "GPIO_16_30") (pintype "power_in"))
    )
    (net (code "223") (name "Net-(U39-GPIO_17)") (class "Default")
      (node (ref "P2") (pin "14") (pinfunction "14_14") (pintype "passive"))
      (node (ref "U39") (pin "29") (pinfunction "GPIO_17_29") (pintype "power_in"))
    )
    (net (code "224") (name "Net-(U39-MISO{slash}19)") (class "Default")
      (node (ref "P2") (pin "9") (pinfunction "9_9") (pintype "passive"))
      (node (ref "U39") (pin "24") (pinfunction "MISO/19_24") (pintype "power_in"))
    )
    (net (code "225") (name "Net-(U39-MOSI{slash}23)") (class "Default")
      (node (ref "P2") (pin "10") (pinfunction "10_10") (pintype "passive"))
      (node (ref "U39") (pin "25") (pinfunction "MOSI/23_25") (pintype "power_in"))
    )
    (net (code "226") (name "Net-(U39-RX{slash}2)") (class "Default")
      (node (ref "P2") (pin "3") (pinfunction "3_3") (pintype "passive"))
      (node (ref "U39") (pin "18") (pinfunction "RX/2_18") (pintype "power_in"))
    )
    (net (code "227") (name "Net-(U39-SCK{slash}18)") (class "Default")
      (node (ref "P2") (pin "11") (pinfunction "11_11") (pintype "passive"))
      (node (ref "U39") (pin "26") (pinfunction "SCK/18_26") (pintype "power_in"))
    )
    (net (code "228") (name "Net-(U39-SS{slash}5{slash}LED)") (class "Default")
      (node (ref "P2") (pin "12") (pinfunction "12_12") (pintype "passive"))
      (node (ref "U39") (pin "27") (pinfunction "SS/5/LED_27") (pintype "power_in"))
    )
    (net (code "229") (name "Net-(U39-TX{slash}1)") (class "Default")
      (node (ref "P2") (pin "2") (pinfunction "2_2") (pintype "passive"))
      (node (ref "U39") (pin "17") (pinfunction "TX/1_17") (pintype "power_in"))
    )
    (net (code "230") (name "RPdrvS1") (class "Default")
      (node (ref "D16") (pin "2") (pinfunction "A_2") (pintype "passive"))
    )
    (net (code "231") (name "RPdrvS2") (class "Default")
      (node (ref "D19") (pin "2") (pinfunction "A_2") (pintype "passive"))
    )
    (net (code "232") (name "RPdrvS3") (class "Default")
      (node (ref "D20") (pin "2") (pinfunction "A_2") (pintype "passive"))
    )
    (net (code "233") (name "RPdrvS4") (class "Default")
      (node (ref "D21") (pin "2") (pinfunction "A_2") (pintype "passive"))
    )
    (net (code "234") (name "RPdrvS5") (class "Default")
      (node (ref "D22") (pin "2") (pinfunction "A_2") (pintype "passive"))
    )
    (net (code "235") (name "RPdrvS6") (class "Default")
      (node (ref "D23") (pin "2") (pinfunction "A_2") (pintype "passive"))
    )
    (net (code "236") (name "RPdrvS7") (class "Default")
      (node (ref "D24") (pin "2") (pinfunction "A_2") (pintype "passive"))
    )
    (net (code "237") (name "RPdrvS8") (class "Default")
      (node (ref "D25") (pin "2") (pinfunction "A_2") (pintype "passive"))
    )
    (net (code "238") (name "SCLA") (class "Default")
      (node (ref "I2C") (pin "1") (pinfunction "1_1") (pintype "passive"))
      (node (ref "P2") (pin "5") (pinfunction "5_5") (pintype "passive"))
      (node (ref "R187") (pin "2") (pinfunction "2_2") (pintype "passive"))
      (node (ref "R258") (pin "1") (pinfunction "1_1") (pintype "passive"))
      (node (ref "R311") (pin "2") (pinfunction "2_2") (pintype "passive"))
      (node (ref "U39") (pin "20") (pinfunction "SCL/22_20") (pintype "power_in"))
    )
    (net (code "239") (name "SDAA") (class "Default")
      (node (ref "I2C") (pin "2") (pinfunction "2_2") (pintype "passive"))
      (node (ref "P2") (pin "6") (pinfunction "6_6") (pintype "passive"))
      (node (ref "R173") (pin "2") (pinfunction "2_2") (pintype "passive"))
      (node (ref "R259") (pin "1") (pinfunction "1_1") (pintype "passive"))
      (node (ref "R310") (pin "2") (pinfunction "2_2") (pintype "passive"))
      (node (ref "U39") (pin "21") (pinfunction "SDA/21_21") (pintype "power_in"))
    )
    (net (code "240") (name "Vbias_1_25") (class "Default")
      (node (ref "R245") (pin "1") (pinfunction "1_1") (pintype "passive"))
    )
    (net (code "241") (name "VoutS1") (class "Default")
      (node (ref "R250") (pin "1") (pinfunction "1_1") (pintype "passive"))
    )
    (net (code "242") (name "VoutS2") (class "Default")
      (node (ref "R252") (pin "1") (pinfunction "1_1") (pintype "passive"))
    )
    (net (code "243") (name "VoutS3") (class "Default")
      (node (ref "R47") (pin "1") (pinfunction "1_1") (pintype "passive"))
    )
    (net (code "244") (name "VoutS4") (class "Default")
      (node (ref "R51") (pin "1") (pinfunction "1_1") (pintype "passive"))
    )
    (net (code "245") (name "VoutS5") (class "Default")
      (node (ref "R53") (pin "1") (pinfunction "1_1") (pintype "passive"))
    )
    (net (code "246") (name "VoutS6") (class "Default")
      (node (ref "R254") (pin "1") (pinfunction "1_1") (pintype "passive"))
    )
    (net (code "247") (name "VoutS7") (class "Default")
      (node (ref "R256") (pin "1") (pinfunction "1_1") (pintype "passive"))
    )
    (net (code "248") (name "VoutS8") (class "Default")
      (node (ref "R55") (pin "1") (pinfunction "1_1") (pintype "passive"))
    )
    (net (code "249") (name "unconnected-(J5-Pad2)") (class "Default")
      (node (ref "J5") (pin "2") (pinfunction "2_2") (pintype "passive+no_connect"))
    )
    (net (code "250") (name "unconnected-(J5-Pad3)") (class "Default")
      (node (ref "J5") (pin "3") (pinfunction "3_3") (pintype "passive+no_connect"))
    )
    (net (code "251") (name "unconnected-(J5-Pad4)") (class "Default")
      (node (ref "J5") (pin "4") (pinfunction "4_4") (pintype "passive+no_connect"))
    )
    (net (code "252") (name "unconnected-(J5-Pad5)") (class "Default")
      (node (ref "J5") (pin "5") (pinfunction "5_5") (pintype "passive+no_connect"))
    )
    (net (code "253") (name "unconnected-(J5-Pad6)") (class "Default")
      (node (ref "J5") (pin "6") (pinfunction "6_6") (pintype "passive+no_connect"))
    )
    (net (code "254") (name "unconnected-(J5-Pad7)") (class "Default")
      (node (ref "J5") (pin "7") (pinfunction "7_7") (pintype "passive+no_connect"))
    )
    (net (code "255") (name "unconnected-(J5-Pad8)") (class "Default")
      (node (ref "J5") (pin "8") (pinfunction "8_8") (pintype "passive+no_connect"))
    )
    (net (code "256") (name "unconnected-(J5-Pad47)") (class "Default")
      (node (ref "J5") (pin "47") (pinfunction "47_47") (pintype "passive+no_connect"))
    )
    (net (code "257") (name "unconnected-(J5-Pad51)") (class "Default")
      (node (ref "J5") (pin "51") (pinfunction "51_51") (pintype "passive+no_connect"))
    )
    (net (code "258") (name "unconnected-(J5-Pad55)") (class "Default")
      (node (ref "J5") (pin "55") (pinfunction "55_55") (pintype "passive+no_connect"))
    )
    (net (code "259") (name "unconnected-(J5-Pad76)") (class "Default")
      (node (ref "J5") (pin "76") (pinfunction "76_76") (pintype "passive+no_connect"))
    )
    (net (code "260") (name "unconnected-(J5-Pad77)") (class "Default")
      (node (ref "J5") (pin "77") (pinfunction "77_77") (pintype "passive+no_connect"))
    )
    (net (code "261") (name "unconnected-(J5-Pad78)") (class "Default")
      (node (ref "J5") (pin "78") (pinfunction "78_78") (pintype "passive+no_connect"))
    )
    (net (code "262") (name "unconnected-(J5-Pad79)") (class "Default")
      (node (ref "J5") (pin "79") (pinfunction "79_79") (pintype "passive+no_connect"))
    )
    (net (code "263") (name "unconnected-(J5-Pad80)") (class "Default")
      (node (ref "J5") (pin "80") (pinfunction "80_80") (pintype "passive+no_connect"))
    )
    (net (code "264") (name "unconnected-(J5-Pad89)") (class "Default")
      (node (ref "J5") (pin "89") (pinfunction "89_89") (pintype "passive+no_connect"))
    )
    (net (code "265") (name "unconnected-(J5-Pad95)") (class "Default")
      (node (ref "J5") (pin "95") (pinfunction "95_95") (pintype "passive+no_connect"))
    )
    (net (code "266") (name "unconnected-(J5-Pad97)") (class "Default")
      (node (ref "J5") (pin "97") (pinfunction "97_97") (pintype "passive+no_connect"))
    )
    (net (code "267") (name "unconnected-(J5-Pad113)") (class "Default")
      (node (ref "J5") (pin "113") (pinfunction "113_113") (pintype "passive"))
    )
    (net (code "268") (name "unconnected-(J5-Pad115)") (class "Default")
      (node (ref "J5") (pin "115") (pinfunction "115_115") (pintype "passive"))
    )
    (net (code "269") (name "unconnected-(J5-Pad116)") (class "Default")
      (node (ref "J5") (pin "116") (pinfunction "116_116") (pintype "passive"))
    )
    (net (code "270") (name "unconnected-(J5-Pad117)") (class "Default")
      (node (ref "J5") (pin "117") (pinfunction "117_117") (pintype "passive"))
    )
    (net (code "271") (name "unconnected-(J5-Pad118)") (class "Default")
      (node (ref "J5") (pin "118") (pinfunction "118_118") (pintype "passive"))
    )
    (net (code "272") (name "unconnected-(J5-Pad119)") (class "Default")
      (node (ref "J5") (pin "119") (pinfunction "119_119") (pintype "passive"))
    )
    (net (code "273") (name "unconnected-(J5-Pad120)") (class "Default")
      (node (ref "J5") (pin "120") (pinfunction "120_120") (pintype "passive"))
    )
    (net (code "274") (name "unconnected-(J6-Pad7)") (class "Default")
      (node (ref "J6") (pin "7") (pinfunction "7_7") (pintype "passive+no_connect"))
    )
    (net (code "275") (name "unconnected-(J6-Pad9)") (class "Default")
      (node (ref "J6") (pin "9") (pinfunction "9_9") (pintype "passive+no_connect"))
    )
    (net (code "276") (name "unconnected-(J7-Pad2)") (class "Default")
      (node (ref "J7") (pin "2") (pinfunction "2_2") (pintype "passive+no_connect"))
    )
    (net (code "277") (name "unconnected-(J7-Pad4)") (class "Default")
      (node (ref "J7") (pin "4") (pinfunction "4_4") (pintype "passive+no_connect"))
    )
    (net (code "278") (name "unconnected-(R58-Pad1)") (class "Default")
      (node (ref "R58") (pin "1") (pinfunction "1_1") (pintype "passive+no_connect"))
    )
    (net (code "279") (name "unconnected-(R246-Pad1)") (class "Default")
      (node (ref "R246") (pin "1") (pinfunction "1_1") (pintype "passive+no_connect"))
    )
    (net (code "280") (name "unconnected-(R248-Pad1)") (class "Default")
      (node (ref "R248") (pin "1") (pinfunction "1_1") (pintype "passive+no_connect"))
    )
    (net (code "281") (name "unconnected-(U17-ANT_SEL1-Pad25)") (class "Default")
      (node (ref "U17") (pin "25") (pinfunction "ANT_SEL1_25") (pintype "bidirectional+no_connect"))
    )
    (net (code "282") (name "unconnected-(U17-ANT_SEL2-Pad26)") (class "Default")
      (node (ref "U17") (pin "26") (pinfunction "ANT_SEL2_26") (pintype "bidirectional+no_connect"))
    )
    (net (code "283") (name "unconnected-(U17-GPIO0-Pad44)") (class "Default")
      (node (ref "U17") (pin "44") (pinfunction "GPIO0_44") (pintype "bidirectional"))
    )
    (net (code "284") (name "unconnected-(U17-GPIO1-Pad46)") (class "Default")
      (node (ref "U17") (pin "46") (pinfunction "GPIO1_46") (pintype "bidirectional"))
    )
    (net (code "285") (name "unconnected-(U17-GPIO2-Pad47)") (class "Default")
      (node (ref "U17") (pin "47") (pinfunction "GPIO2_47") (pintype "bidirectional"))
    )
    (net (code "286") (name "unconnected-(U17-GPIO3-Pad48)") (class "Default")
      (node (ref "U17") (pin "48") (pinfunction "GPIO3_48") (pintype "bidirectional"))
    )
    (net (code "287") (name "unconnected-(U17-GPIO4-Pad49)") (class "Default")
      (node (ref "U17") (pin "49") (pinfunction "GPIO4_49") (pintype "bidirectional"))
    )
    (net (code "288") (name "unconnected-(U17-GPIO5-Pad50)") (class "Default")
      (node (ref "U17") (pin "50") (pinfunction "GPIO5_50") (pintype "bidirectional"))
    )
    (net (code "289") (name "unconnected-(U17-GPIO6-Pad51)") (class "Default")
      (node (ref "U17") (pin "51") (pinfunction "GPIO6_51") (pintype "bidirectional"))
    )
    (net (code "290") (name "unconnected-(U17-GPIO7-Pad52)") (class "Default")
      (node (ref "U17") (pin "52") (pinfunction "GPIO7_52") (pintype "bidirectional"))
    )
    (net (code "291") (name "unconnected-(U17-GPIO8-Pad53)") (class "Default")
      (node (ref "U17") (pin "53") (pinfunction "GPIO8_53") (pintype "bidirectional"))
    )
    (net (code "292") (name "unconnected-(U17-GPIO9-Pad54)") (class "Default")
      (node (ref "U17") (pin "54") (pinfunction "GPIO9_54") (pintype "bidirectional"))
    )
    (net (code "293") (name "unconnected-(U17-GPIO10-Pad3)") (class "Default")
      (node (ref "U17") (pin "3") (pinfunction "GPIO10_3") (pintype "bidirectional"))
    )
    (net (code "294") (name "unconnected-(U17-GPIO12-Pad9)") (class "Default")
      (node (ref "U17") (pin "9") (pinfunction "GPIO12_9") (pintype "bidirectional"))
    )
    (net (code "295") (name "unconnected-(U17-GPIO13-Pad10)") (class "Default")
      (node (ref "U17") (pin "10") (pinfunction "GPIO13_10") (pintype "bidirectional"))
    )
    (net (code "296") (name "unconnected-(U17-GPIO15-Pad6)") (class "Default")
      (node (ref "U17") (pin "6") (pinfunction "GPIO15_6") (pintype "bidirectional"))
    )
    (net (code "297") (name "unconnected-(U17-GPIO16-Pad7)") (class "Default")
      (node (ref "U17") (pin "7") (pinfunction "GPIO16_7") (pintype "bidirectional"))
    )
    (net (code "298") (name "unconnected-(U17-GPIO17-Pad8)") (class "Default")
      (node (ref "U17") (pin "8") (pinfunction "GPIO17_8") (pintype "bidirectional"))
    )
    (net (code "299") (name "unconnected-(U17-GPIO22-Pad11)") (class "Default")
      (node (ref "U17") (pin "11") (pinfunction "GPIO22_11") (pintype "bidirectional"))
    )
    (net (code "300") (name "unconnected-(U17-GPIO28-Pad19)") (class "Default")
      (node (ref "U17") (pin "19") (pinfunction "GPIO28_19") (pintype "bidirectional"))
    )
    (net (code "301") (name "unconnected-(U17-GPIO30-Pad42)") (class "Default")
      (node (ref "U17") (pin "42") (pinfunction "GPIO30_42") (pintype "bidirectional"))
    )
    (net (code "302") (name "unconnected-(U17-NC-Pad20)") (class "Default")
      (node (ref "U17") (pin "20") (pinfunction "NC_20") (pintype "passive+no_connect"))
    )
    (net (code "303") (name "unconnected-(U17-NC-Pad29)") (class "Default")
      (node (ref "U17") (pin "29") (pinfunction "NC_29") (pintype "passive+no_connect"))
    )
    (net (code "304") (name "unconnected-(U17-NC-Pad33)") (class "Default")
      (node (ref "U17") (pin "33") (pinfunction "NC_33") (pintype "passive+no_connect"))
    )
    (net (code "305") (name "unconnected-(U17-NC-Pad39)") (class "Default")
      (node (ref "U17") (pin "39") (pinfunction "NC_39") (pintype "passive+no_connect"))
    )
    (net (code "306") (name "unconnected-(U17-NC-Pad41)") (class "Default")
      (node (ref "U17") (pin "41") (pinfunction "NC_41") (pintype "passive+no_connect"))
    )
    (net (code "307") (name "unconnected-(U17-NC-Pad45)") (class "Default")
      (node (ref "U17") (pin "45") (pinfunction "NC_45") (pintype "passive+no_connect"))
    )
    (net (code "308") (name "unconnected-(U17-RF_BG-Pad31)") (class "Default")
      (node (ref "U17") (pin "31") (pinfunction "RF_BG_31") (pintype "bidirectional+no_connect"))
    )
    (net (code "309") (name "unconnected-(U17-VBAT_RESET-Pad36)") (class "Default")
      (node (ref "U17") (pin "36") (pinfunction "VBAT_RESET_36") (pintype "passive+no_connect"))
    )
    (net (code "310") (name "unconnected-(U26-EO-Pad15)") (class "Default")
      (node (ref "U26") (pin "15") (pinfunction "EO_15") (pintype "output+no_connect"))
    )
    (net (code "311") (name "unconnected-(U26-GS-Pad14)") (class "Default")
      (node (ref "U26") (pin "14") (pinfunction "GS_14") (pintype "output+no_connect"))
    )
    (net (code "312") (name "unconnected-(U27-EO-Pad15)") (class "Default")
      (node (ref "U27") (pin "15") (pinfunction "EO_15") (pintype "output+no_connect"))
    )
    (net (code "313") (name "unconnected-(U27-GS-Pad14)") (class "Default")
      (node (ref "U27") (pin "14") (pinfunction "GS_14") (pintype "output+no_connect"))
    )
    (net (code "314") (name "unconnected-(U34-NC-Pad1)") (class "Default")
      (node (ref "U34") (pin "1") (pinfunction "NC_1") (pintype "passive"))
    )
  )
)
